# pc_healthypi_v1.net
KiCad netlist of a schematic drawn in EAGLE
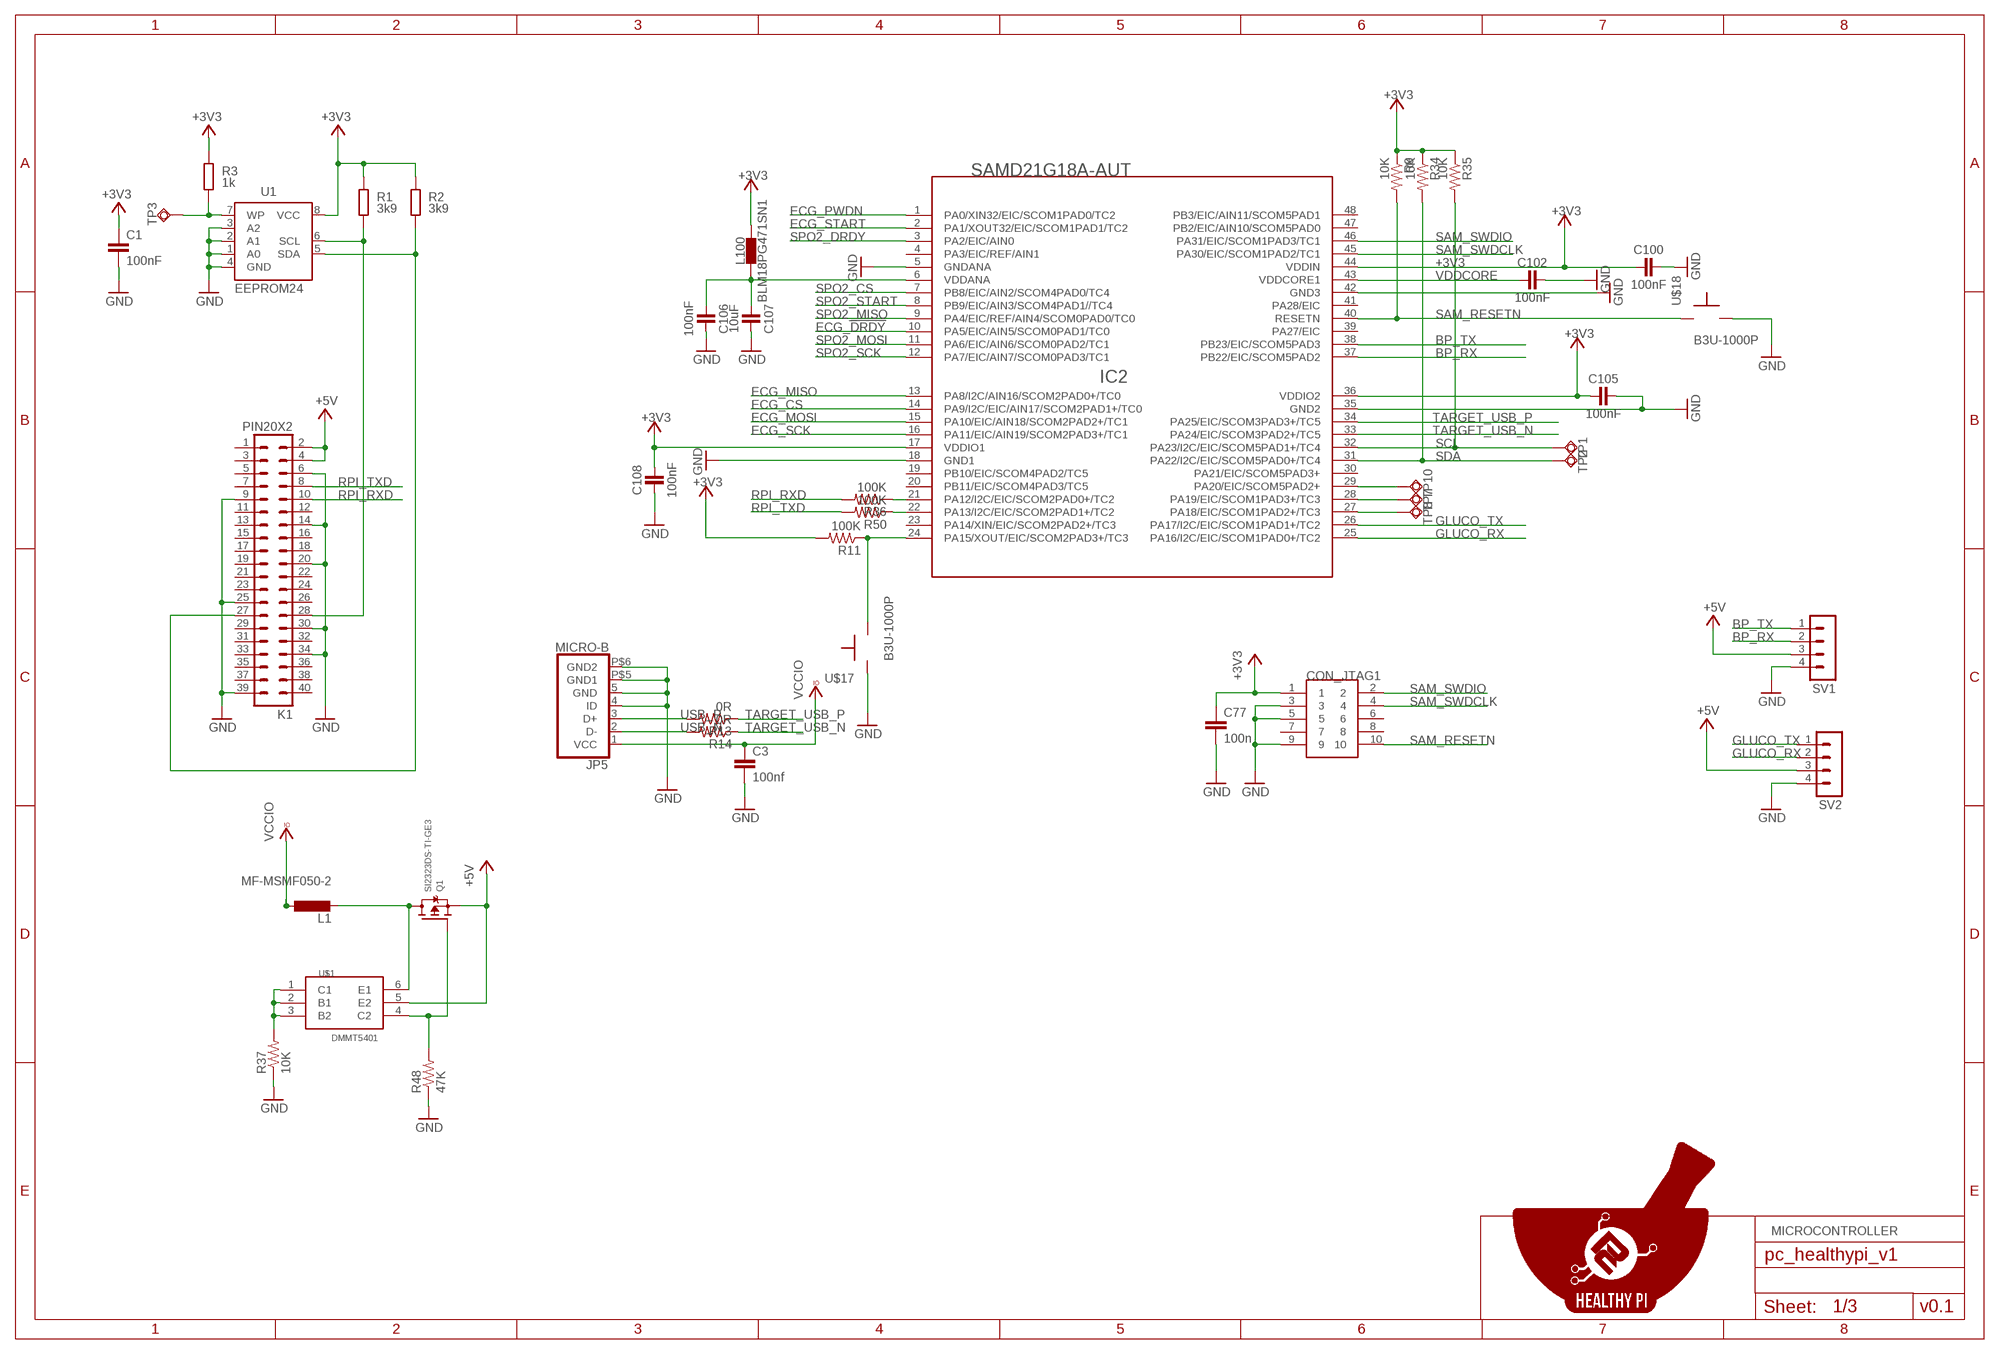
[diagram p0: schematic, sheet 1]
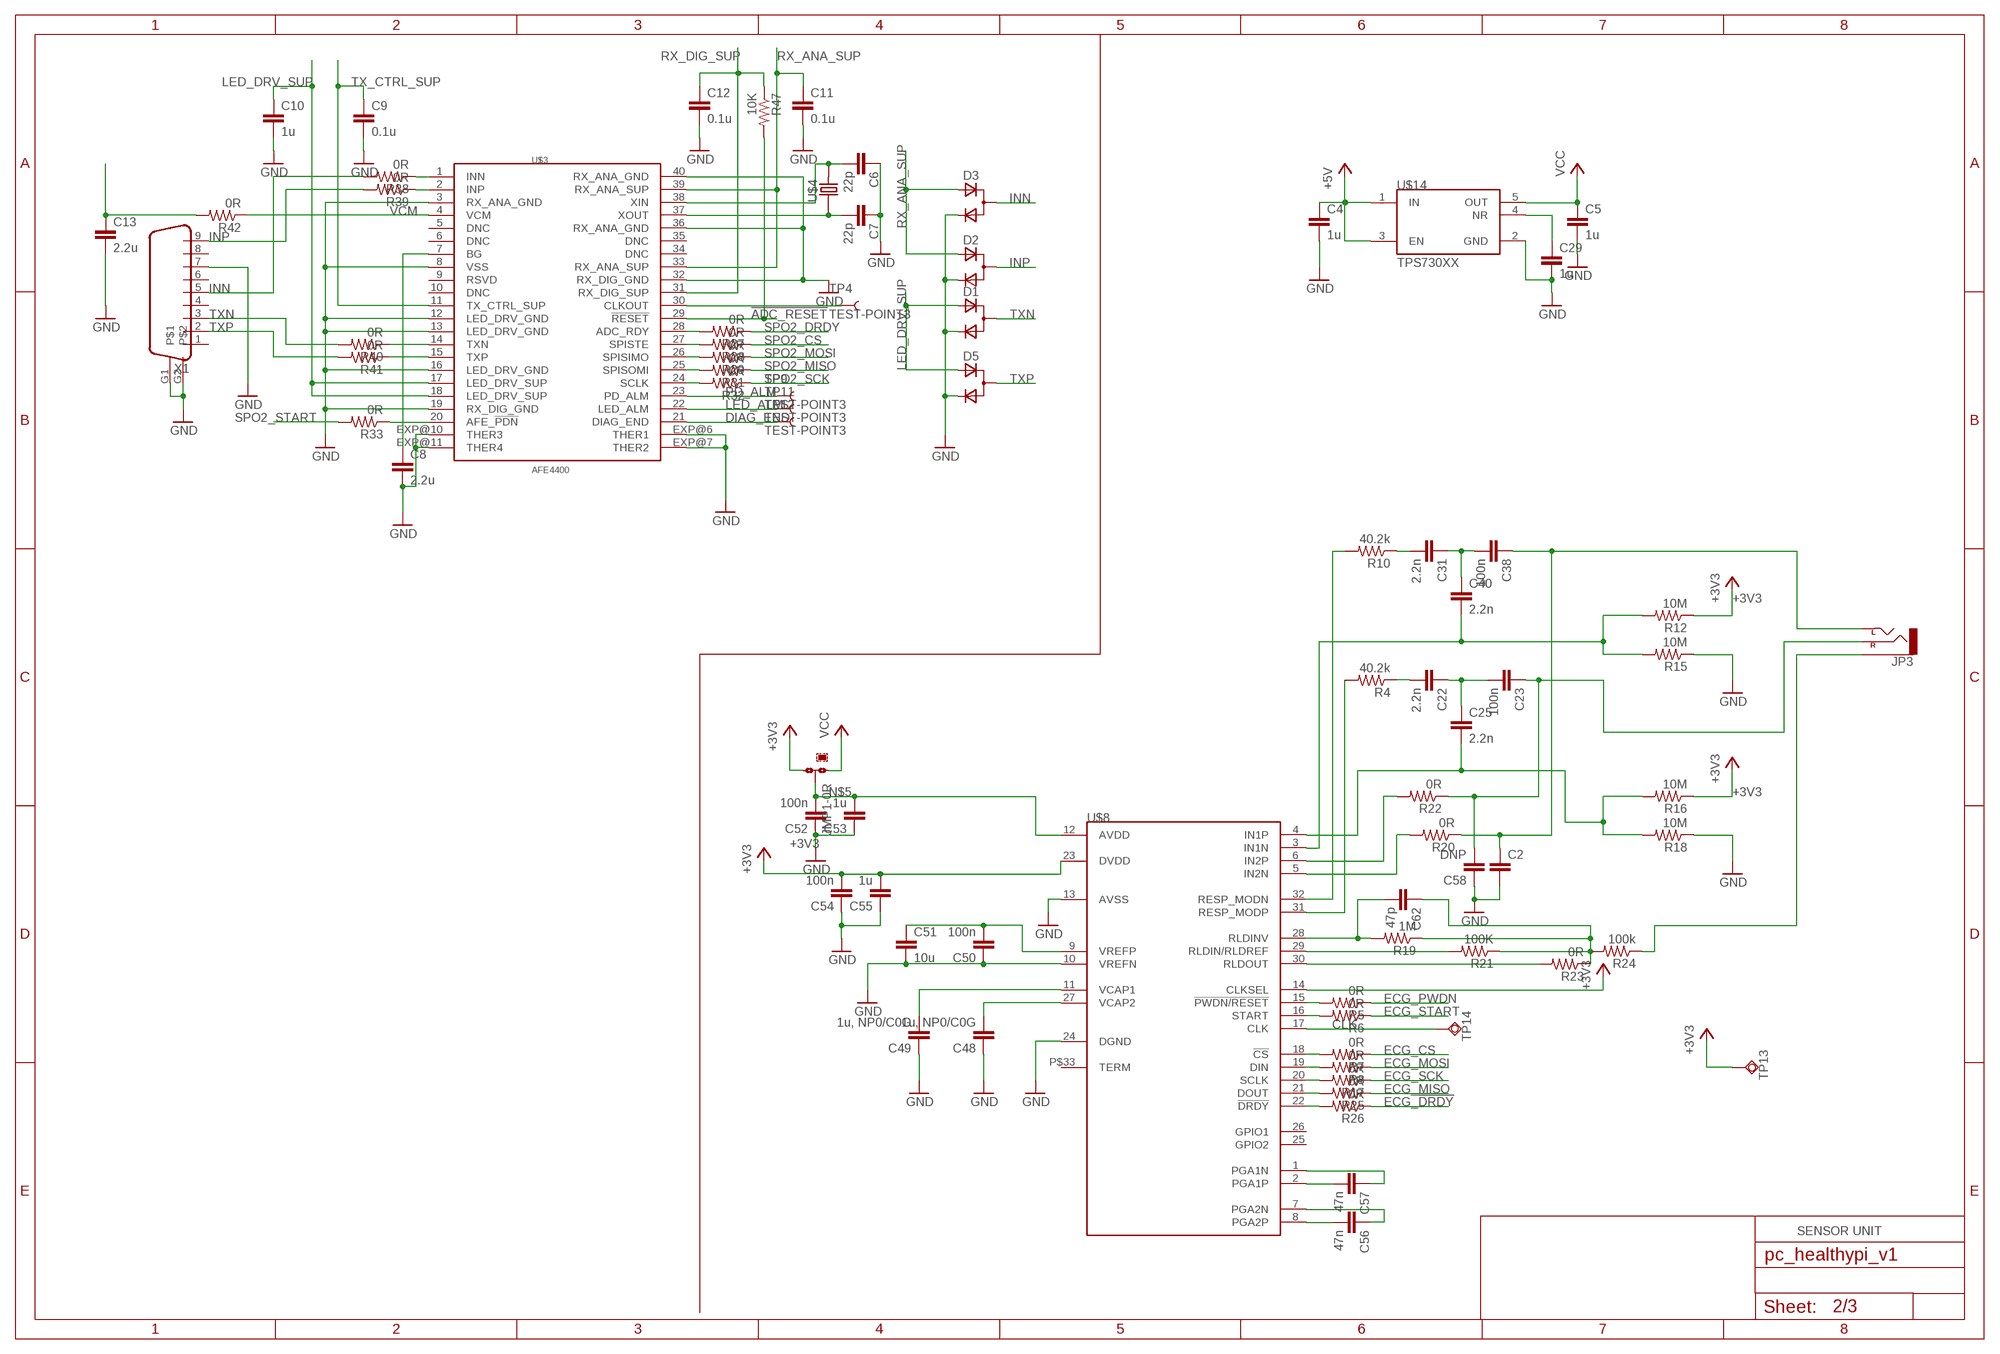
[diagram p1: schematic, sheet 2]
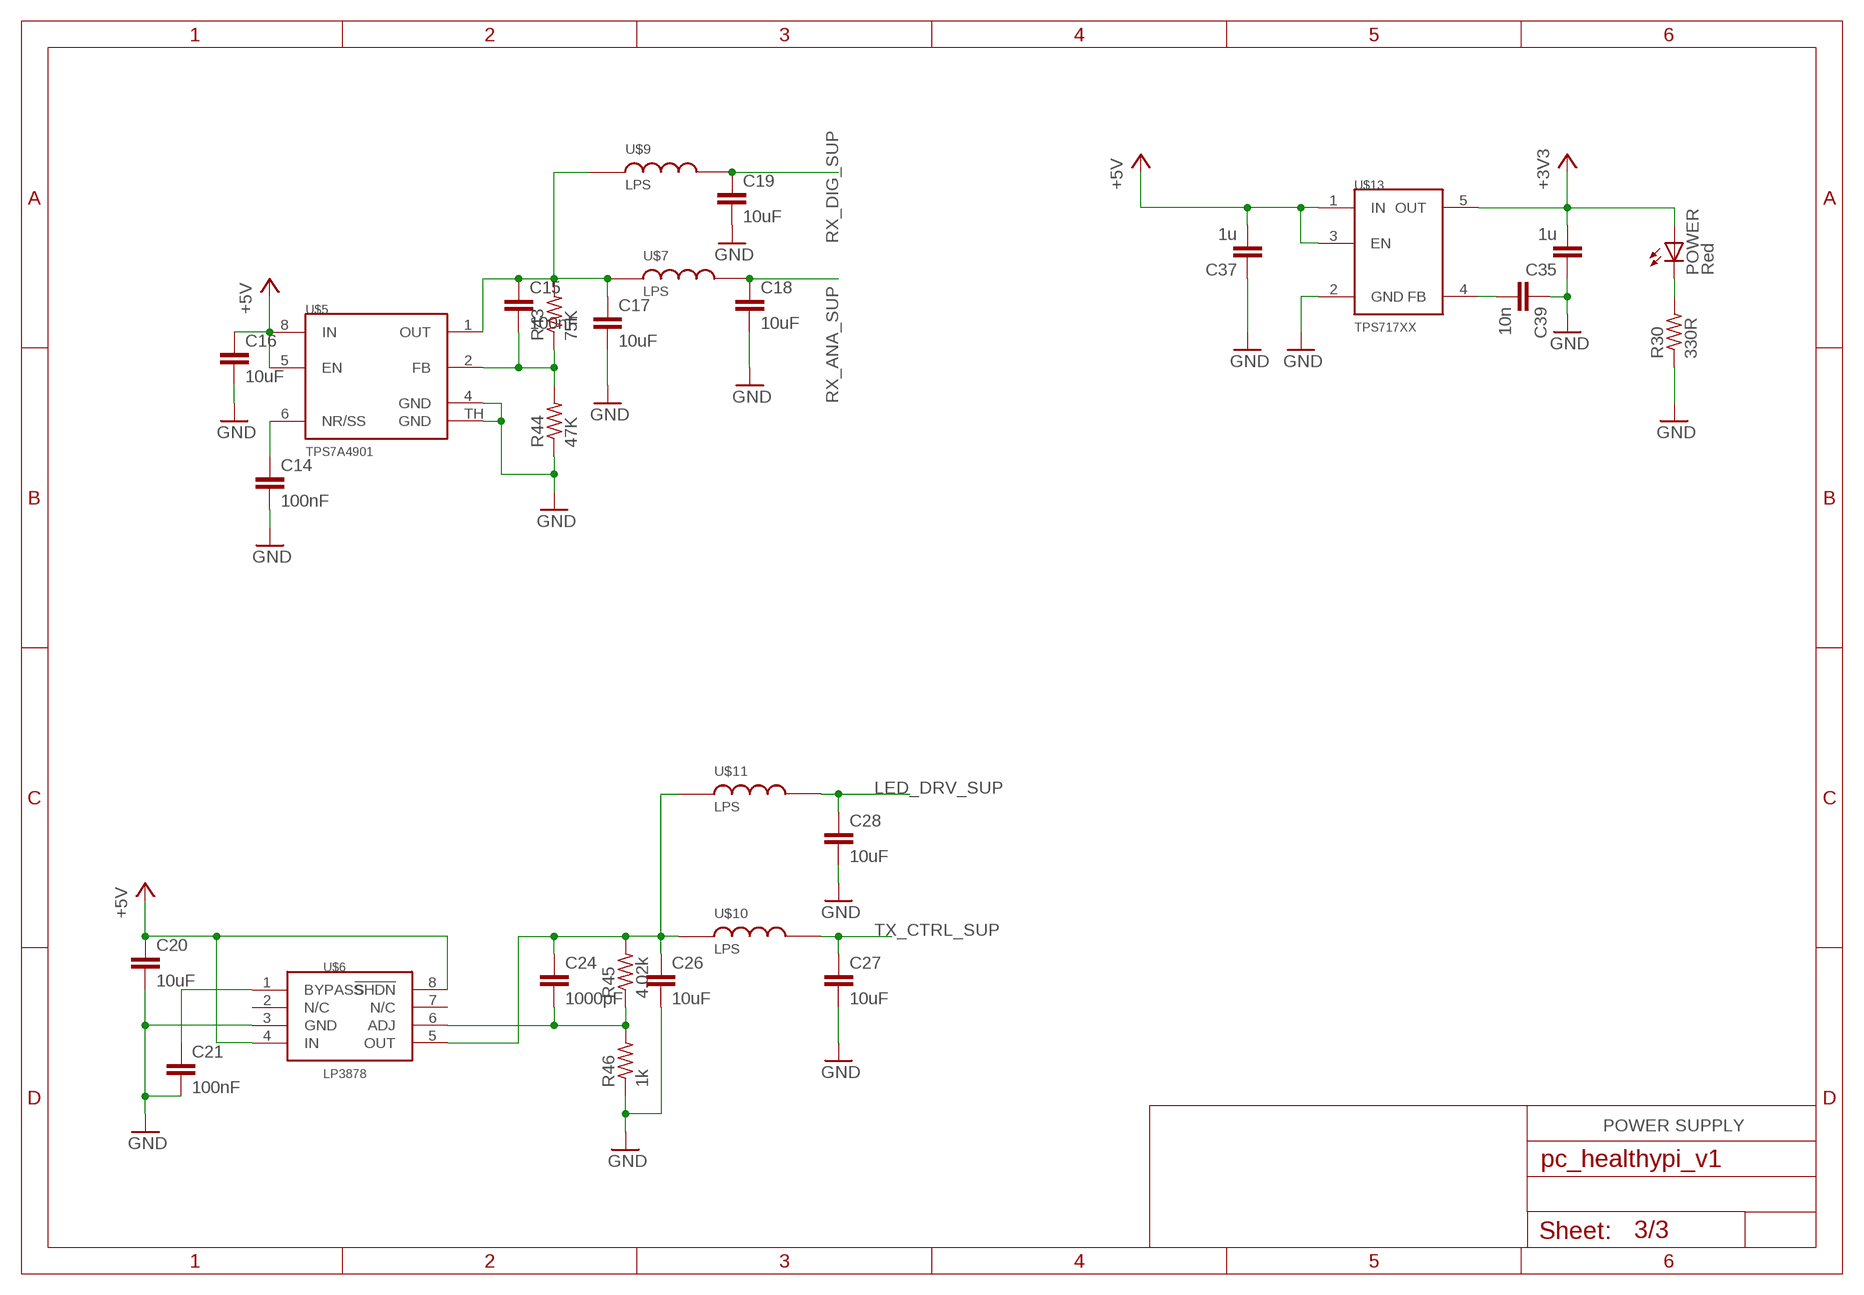
[diagram p2: schematic, sheet 3]

(export (version "E")
  (design (tool "Eeschema 10.0.6"))
  (components
    (comp (ref "C2")
      (value "C-EUC0402")
      (footprint "eagle-import:C0402")
      (libsource (lib "eagle-import") (part "C-EUC0402"))
    )
    (comp (ref "C4")
      (value "1u")
      (footprint "eagle-import:C0402")
      (libsource (lib "eagle-import") (part "C-EUC0402"))
    )
    (comp (ref "C5")
      (value "1u")
      (footprint "eagle-import:C0402")
      (libsource (lib "eagle-import") (part "C-EUC0402"))
    )
    (comp (ref "C6")
      (value "22p")
      (footprint "eagle-import:C0402")
      (libsource (lib "eagle-import") (part "C-EUC0402"))
    )
    (comp (ref "C7")
      (value "22p")
      (footprint "eagle-import:C0402")
      (libsource (lib "eagle-import") (part "C-EUC0402"))
    )
    (comp (ref "C8")
      (value "2.2u")
      (footprint "eagle-import:C0402")
      (libsource (lib "eagle-import") (part "C-EUC0402"))
    )
    (comp (ref "C9")
      (value "0.1u")
      (footprint "eagle-import:C0402")
      (libsource (lib "eagle-import") (part "C-EUC0402"))
    )
    (comp (ref "C10")
      (value "1u")
      (footprint "eagle-import:C0805")
      (libsource (lib "eagle-import") (part "C-EUC0805"))
    )
    (comp (ref "C11")
      (value "0.1u")
      (footprint "eagle-import:C0402")
      (libsource (lib "eagle-import") (part "C-EUC0402"))
    )
    (comp (ref "C12")
      (value "0.1u")
      (footprint "eagle-import:C0402")
      (libsource (lib "eagle-import") (part "C-EUC0402"))
    )
    (comp (ref "C13")
      (value "2.2u")
      (footprint "eagle-import:C0402")
      (libsource (lib "eagle-import") (part "C-EUC0402"))
    )
    (comp (ref "C22")
      (value "2.2n")
      (footprint "eagle-import:C0402")
      (libsource (lib "eagle-import") (part "C-EUC0402"))
    )
    (comp (ref "C23")
      (value "100n")
      (footprint "eagle-import:C0402")
      (libsource (lib "eagle-import") (part "C-EUC0402"))
    )
    (comp (ref "C25")
      (value "2.2n")
      (footprint "eagle-import:C0402")
      (libsource (lib "eagle-import") (part "C-EUC0402"))
    )
    (comp (ref "C29")
      (value "1u")
      (footprint "eagle-import:C0402")
      (libsource (lib "eagle-import") (part "C-EUC0402"))
    )
    (comp (ref "C31")
      (value "2.2n")
      (footprint "eagle-import:C0402")
      (libsource (lib "eagle-import") (part "C-EUC0402"))
    )
    (comp (ref "C38")
      (value "100n")
      (footprint "eagle-import:C0402")
      (libsource (lib "eagle-import") (part "C-EUC0402"))
    )
    (comp (ref "C40")
      (value "2.2n")
      (footprint "eagle-import:C0402")
      (libsource (lib "eagle-import") (part "C-EUC0402"))
    )
    (comp (ref "C48")
      (value "1u, NP0/C0G")
      (footprint "eagle-import:C0402")
      (libsource (lib "eagle-import") (part "C-EUC0402"))
    )
    (comp (ref "C49")
      (value "1u, NP0/C0G")
      (footprint "eagle-import:C0402")
      (libsource (lib "eagle-import") (part "C-EUC0402"))
    )
    (comp (ref "C50")
      (value "100n")
      (footprint "eagle-import:C0402")
      (libsource (lib "eagle-import") (part "C-EUC0402"))
    )
    (comp (ref "C51")
      (value "10u")
      (footprint "eagle-import:C0603")
      (libsource (lib "eagle-import") (part "resistor_C-EUC0603"))
    )
    (comp (ref "C52")
      (value "100n")
      (footprint "eagle-import:C0402")
      (libsource (lib "eagle-import") (part "C-EUC0402"))
    )
    (comp (ref "C53")
      (value "1u")
      (footprint "eagle-import:C0402")
      (libsource (lib "eagle-import") (part "C-EUC0402"))
    )
    (comp (ref "C54")
      (value "100n")
      (footprint "eagle-import:C0402")
      (libsource (lib "eagle-import") (part "C-EUC0402"))
    )
    (comp (ref "C55")
      (value "1u")
      (footprint "eagle-import:C0402")
      (libsource (lib "eagle-import") (part "C-EUC0402"))
    )
    (comp (ref "C56")
      (value "47n")
      (footprint "eagle-import:C0402")
      (libsource (lib "eagle-import") (part "C-EUC0402"))
    )
    (comp (ref "C57")
      (value "47n")
      (footprint "eagle-import:C0402")
      (libsource (lib "eagle-import") (part "C-EUC0402"))
    )
    (comp (ref "C58")
      (value "DNP")
      (footprint "eagle-import:C0402")
      (libsource (lib "eagle-import") (part "C-EUC0402"))
    )
    (comp (ref "C62")
      (value "47p")
      (footprint "eagle-import:C0402")
      (libsource (lib "eagle-import") (part "C-EUC0402"))
    )
    (comp (ref "D1")
      (value "D_ACACSOT323")
      (footprint "eagle-import:SOT323")
      (libsource (lib "eagle-import") (part "D_ACACSOT323"))
    )
    (comp (ref "D2")
      (value "D_ACACSOT323")
      (footprint "eagle-import:SOT323")
      (libsource (lib "eagle-import") (part "D_ACACSOT323"))
    )
    (comp (ref "D3")
      (value "D_ACACSOT323")
      (footprint "eagle-import:SOT323")
      (libsource (lib "eagle-import") (part "D_ACACSOT323"))
    )
    (comp (ref "D5")
      (value "D_ACACSOT323")
      (footprint "eagle-import:SOT323")
      (libsource (lib "eagle-import") (part "D_ACACSOT323"))
    )
    (comp (ref "JMP1")
      (value "0R-JUMPB")
      (footprint "eagle-import:B0R-JMP")
      (libsource (lib "eagle-import") (part "0R-JUMPB"))
    )
    (comp (ref "JP3")
      (value "AUDIO-JACKSMD2")
      (footprint "eagle-import:AUDIO-JACK-3.5MM-SMD")
      (libsource (lib "eagle-import") (part "AUDIO-JACKSMD2"))
    )
    (comp (ref "R4")
      (value "40.2k")
      (footprint "eagle-import:R0402")
      (libsource (lib "eagle-import") (part "R-US_R0402"))
    )
    (comp (ref "R5")
      (value "0R")
      (footprint "eagle-import:R0402")
      (libsource (lib "eagle-import") (part "R-US_R0402"))
    )
    (comp (ref "R6")
      (value "0R")
      (footprint "eagle-import:R0402")
      (libsource (lib "eagle-import") (part "R-US_R0402"))
    )
    (comp (ref "R7")
      (value "0R")
      (footprint "eagle-import:R0402")
      (libsource (lib "eagle-import") (part "R-US_R0402"))
    )
    (comp (ref "R8")
      (value "0R")
      (footprint "eagle-import:R0402")
      (libsource (lib "eagle-import") (part "R-US_R0402"))
    )
    (comp (ref "R10")
      (value "40.2k")
      (footprint "eagle-import:R0402")
      (libsource (lib "eagle-import") (part "R-US_R0402"))
    )
    (comp (ref "R12")
      (value "10M")
      (footprint "eagle-import:R0402")
      (libsource (lib "eagle-import") (part "R-US_R0402"))
    )
    (comp (ref "R15")
      (value "10M")
      (footprint "eagle-import:R0402")
      (libsource (lib "eagle-import") (part "R-US_R0402"))
    )
    (comp (ref "R16")
      (value "10M")
      (footprint "eagle-import:R0402")
      (libsource (lib "eagle-import") (part "R-US_R0402"))
    )
    (comp (ref "R17")
      (value "0R")
      (footprint "eagle-import:R0402")
      (libsource (lib "eagle-import") (part "R-US_R0402"))
    )
    (comp (ref "R18")
      (value "10M")
      (footprint "eagle-import:R0402")
      (libsource (lib "eagle-import") (part "R-US_R0402"))
    )
    (comp (ref "R19")
      (value "1M")
      (footprint "eagle-import:R0402")
      (libsource (lib "eagle-import") (part "R-US_R0402"))
    )
    (comp (ref "R20")
      (value "0R")
      (footprint "eagle-import:R0402")
      (libsource (lib "eagle-import") (part "R-US_R0402"))
    )
    (comp (ref "R21")
      (value "100K")
      (footprint "eagle-import:R0402")
      (libsource (lib "eagle-import") (part "R-US_R0402"))
    )
    (comp (ref "R22")
      (value "0R")
      (footprint "eagle-import:R0402")
      (libsource (lib "eagle-import") (part "R-US_R0402"))
    )
    (comp (ref "R23")
      (value "0R")
      (footprint "eagle-import:R0402")
      (libsource (lib "eagle-import") (part "R-US_R0402"))
    )
    (comp (ref "R24")
      (value "100k")
      (footprint "eagle-import:R0402")
      (libsource (lib "eagle-import") (part "R-US_R0402"))
    )
    (comp (ref "R25")
      (value "0R")
      (footprint "eagle-import:R0402")
      (libsource (lib "eagle-import") (part "R-US_R0402"))
    )
    (comp (ref "R26")
      (value "0R")
      (footprint "eagle-import:R0402")
      (libsource (lib "eagle-import") (part "R-US_R0402"))
    )
    (comp (ref "R27")
      (value "0R")
      (footprint "eagle-import:R0402")
      (libsource (lib "eagle-import") (part "R-US_R0402"))
    )
    (comp (ref "R28")
      (value "0R")
      (footprint "eagle-import:R0402")
      (libsource (lib "eagle-import") (part "R-US_R0402"))
    )
    (comp (ref "R29")
      (value "0R")
      (footprint "eagle-import:R0402")
      (libsource (lib "eagle-import") (part "R-US_R0402"))
    )
    (comp (ref "R31")
      (value "0R")
      (footprint "eagle-import:R0402")
      (libsource (lib "eagle-import") (part "R-US_R0402"))
    )
    (comp (ref "R32")
      (value "0R")
      (footprint "eagle-import:R0402")
      (libsource (lib "eagle-import") (part "R-US_R0402"))
    )
    (comp (ref "R33")
      (value "0R")
      (footprint "eagle-import:R0402")
      (libsource (lib "eagle-import") (part "R-US_R0402"))
    )
    (comp (ref "R38")
      (value "0R")
      (footprint "eagle-import:R0402")
      (libsource (lib "eagle-import") (part "R-US_R0402"))
    )
    (comp (ref "R39")
      (value "0R")
      (footprint "eagle-import:R0402")
      (libsource (lib "eagle-import") (part "R-US_R0402"))
    )
    (comp (ref "R40")
      (value "0R")
      (footprint "eagle-import:R0402")
      (libsource (lib "eagle-import") (part "R-US_R0402"))
    )
    (comp (ref "R41")
      (value "0R")
      (footprint "eagle-import:R0402")
      (libsource (lib "eagle-import") (part "R-US_R0402"))
    )
    (comp (ref "R42")
      (value "0R")
      (footprint "eagle-import:R0402")
      (libsource (lib "eagle-import") (part "R-US_R0402"))
    )
    (comp (ref "R47")
      (value "10K")
      (footprint "eagle-import:R0402")
      (libsource (lib "eagle-import") (part "R-US_R0402"))
    )
    (comp (ref "TP4")
      (value "TEST-POINT3")
      (footprint "eagle-import:PAD.03X.03")
      (libsource (lib "eagle-import") (part "TEST-POINT3"))
    )
    (comp (ref "TP9")
      (value "TEST-POINT3")
      (footprint "eagle-import:PAD.03X.03")
      (libsource (lib "eagle-import") (part "TEST-POINT3"))
    )
    (comp (ref "TP11")
      (value "TEST-POINT3")
      (footprint "eagle-import:PAD.03X.03")
      (libsource (lib "eagle-import") (part "TEST-POINT3"))
    )
    (comp (ref "TP12")
      (value "TEST-POINT3")
      (footprint "eagle-import:PAD.03X.03")
      (libsource (lib "eagle-import") (part "TEST-POINT3"))
    )
    (comp (ref "TP13")
      (value "TPSQB1,27")
      (footprint "eagle-import:B1,27")
      (libsource (lib "eagle-import") (part "TPSQB1,27"))
    )
    (comp (ref "TP14")
      (value "TPSQB1,27")
      (footprint "eagle-import:B1,27")
      (libsource (lib "eagle-import") (part "TPSQB1,27"))
    )
    (comp (ref "U$3")
      (value "AFE4400")
      (footprint "eagle-import:QFN-40")
      (libsource (lib "eagle-import") (part "AFE4400"))
    )
    (comp (ref "U$4")
      (value "ABM3")
      (footprint "eagle-import:ABM3")
      (libsource (lib "eagle-import") (part "ABM3"))
    )
    (comp (ref "U$8")
      (value "ADS1292RPVQFN32")
      (footprint "eagle-import:S-PVQFN-N32")
      (libsource (lib "eagle-import") (part "ADS1292RPVQFN32"))
    )
    (comp (ref "U$14")
      (value "TPS730XX")
      (footprint "eagle-import:SOT23-DBV")
      (libsource (lib "eagle-import") (part "TPS730XX"))
    )
    (comp (ref "X1")
      (value "DB9")
      (footprint "eagle-import:DB9")
      (libsource (lib "eagle-import") (part "DB9"))
    )
    (comp (ref "C1")
      (value "100nF")
      (footprint "eagle-import:C0805K")
      (libsource (lib "eagle-import") (part "resistor_C-EUC0805K"))
    )
    (comp (ref "C3")
      (value "100nf")
      (footprint "eagle-import:C0402")
      (libsource (lib "eagle-import") (part "C-EUC0402"))
    )
    (comp (ref "C77")
      (value "100n")
      (footprint "eagle-import:C0805")
      (libsource (lib "eagle-import") (part "C-EUC0805"))
    )
    (comp (ref "C100")
      (value "100nF")
      (footprint "eagle-import:C0805")
      (libsource (lib "eagle-import") (part "CAPACITORS-0805"))
    )
    (comp (ref "C102")
      (value "100nF")
      (footprint "eagle-import:C0805")
      (libsource (lib "eagle-import") (part "CAPACITORS-0805"))
    )
    (comp (ref "C105")
      (value "100nF")
      (footprint "eagle-import:C0805")
      (libsource (lib "eagle-import") (part "CAPACITORS-0805"))
    )
    (comp (ref "C106")
      (value "100nF")
      (footprint "eagle-import:C0805")
      (libsource (lib "eagle-import") (part "CAPACITORS-0805"))
    )
    (comp (ref "C107")
      (value "10uF")
      (footprint "eagle-import:C0805")
      (libsource (lib "eagle-import") (part "CAPACITORS-0805"))
    )
    (comp (ref "C108")
      (value "100nF")
      (footprint "eagle-import:C0805")
      (libsource (lib "eagle-import") (part "CAPACITORS-0805"))
    )
    (comp (ref "CON_JTAG1")
      (value "HDR-SMT-50MIL/5X2")
      (footprint "eagle-import:HDR-SMT-50MIL_5X2")
      (libsource (lib "eagle-import") (part "HDR-SMT-50MIL/5X2"))
    )
    (comp (ref "IC2")
      (value "SAMD21G18A-AUT")
      (footprint "eagle-import:TQFP48")
      (libsource (lib "eagle-import") (part "SAMD21G18A"))
    )
    (comp (ref "JP5")
      (value "MICRO-B")
      (footprint "eagle-import:MICRO-B")
      (libsource (lib "eagle-import") (part "MICRO-B"))
    )
    (comp (ref "K1")
      (value "PIN20X2")
      (footprint "eagle-import:PIN_20X2")
      (libsource (lib "eagle-import") (part "PIN20X2"))
    )
    (comp (ref "L1")
      (value "MF-MSMF050-2")
      (footprint "eagle-import:L1812")
      (libsource (lib "eagle-import") (part "L-EUL1812"))
    )
    (comp (ref "L100")
      (value "BLM18PG471SN1")
      (footprint "eagle-import:C0603")
      (libsource (lib "eagle-import") (part "INDUCTOR-0603"))
    )
    (comp (ref "Q1")
      (value "SI2323DS-TI-GE3")
      (footprint "eagle-import:SOT23-R")
      (libsource (lib "eagle-import") (part "MOSFET-P"))
    )
    (comp (ref "R1")
      (value "3k9")
      (footprint "eagle-import:M0805")
      (fields (field (name "TOLERANCE") "5%"))
      (libsource (lib "eagle-import") (part "R-EU_M0805"))
    )
    (comp (ref "R2")
      (value "3k9")
      (footprint "eagle-import:M0805")
      (fields (field (name "TOLERANCE") "5%"))
      (libsource (lib "eagle-import") (part "R-EU_M0805"))
    )
    (comp (ref "R3")
      (value "1k")
      (footprint "eagle-import:M0805")
      (fields (field (name "TOLERANCE") "5%"))
      (libsource (lib "eagle-import") (part "R-EU_M0805"))
    )
    (comp (ref "R9")
      (value "10K")
      (footprint "eagle-import:R0805")
      (libsource (lib "eagle-import") (part "R-US_R0805"))
    )
    (comp (ref "R11")
      (value "100K")
      (footprint "eagle-import:R0805")
      (libsource (lib "eagle-import") (part "R-US_R0805"))
    )
    (comp (ref "R13")
      (value "0R")
      (footprint "eagle-import:R0402")
      (libsource (lib "eagle-import") (part "R-US_R0402"))
    )
    (comp (ref "R14")
      (value "0R")
      (footprint "eagle-import:R0402")
      (libsource (lib "eagle-import") (part "R-US_R0402"))
    )
    (comp (ref "R34")
      (value "10K")
      (footprint "eagle-import:R0805")
      (libsource (lib "eagle-import") (part "R-US_R0805"))
    )
    (comp (ref "R35")
      (value "10K")
      (footprint "eagle-import:R0805")
      (libsource (lib "eagle-import") (part "R-US_R0805"))
    )
    (comp (ref "R36")
      (value "100K")
      (footprint "eagle-import:R0402")
      (libsource (lib "eagle-import") (part "R-US_R0402"))
    )
    (comp (ref "R37")
      (value "10K")
      (footprint "eagle-import:R0805")
      (libsource (lib "eagle-import") (part "R-US_R0805"))
    )
    (comp (ref "R48")
      (value "47K")
      (footprint "eagle-import:R0805")
      (libsource (lib "eagle-import") (part "R-US_R0805"))
    )
    (comp (ref "R50")
      (value "100K")
      (footprint "eagle-import:R0402")
      (libsource (lib "eagle-import") (part "R-US_R0402"))
    )
    (comp (ref "SV1")
      (value "MA04-1")
      (footprint "eagle-import:MA04-1")
      (libsource (lib "eagle-import") (part "MA04-1"))
    )
    (comp (ref "SV2")
      (value "MA04-1")
      (footprint "eagle-import:MA04-1")
      (libsource (lib "eagle-import") (part "MA04-1"))
    )
    (comp (ref "TP1")
      (value "TPSQB1,27")
      (footprint "eagle-import:B1,27")
      (libsource (lib "eagle-import") (part "TPSQB1,27"))
    )
    (comp (ref "TP2")
      (value "TPSQB1,27")
      (footprint "eagle-import:B1,27")
      (libsource (lib "eagle-import") (part "TPSQB1,27"))
    )
    (comp (ref "TP3")
      (value "TPSQB1,27")
      (footprint "eagle-import:B1,27")
      (libsource (lib "eagle-import") (part "TPSQB1,27"))
    )
    (comp (ref "TP7")
      (value "TPSQB1,27")
      (footprint "eagle-import:B1,27")
      (libsource (lib "eagle-import") (part "TPSQB1,27"))
    )
    (comp (ref "TP8")
      (value "TPSQB1,27")
      (footprint "eagle-import:B1,27")
      (libsource (lib "eagle-import") (part "TPSQB1,27"))
    )
    (comp (ref "TP10")
      (value "TPSQB1,27")
      (footprint "eagle-import:B1,27")
      (libsource (lib "eagle-import") (part "TPSQB1,27"))
    )
    (comp (ref "U$1")
      (value "DMMT5401")
      (footprint "eagle-import:SOT26")
      (libsource (lib "eagle-import") (part "DMMT5401"))
    )
    (comp (ref "U$15")
      (value "HEALTHYPI")
      (footprint "eagle-import:HEALTHYPI")
      (libsource (lib "eagle-import") (part "HEALTHYPI"))
    )
    (comp (ref "U$17")
      (value "B3U-1000P")
      (footprint "eagle-import:B3U-1000P")
      (libsource (lib "eagle-import") (part "B3U-1000P"))
    )
    (comp (ref "U$18")
      (value "B3U-1000P")
      (footprint "eagle-import:B3U-1000P")
      (libsource (lib "eagle-import") (part "B3U-1000P"))
    )
    (comp (ref "U1")
      (value "EEPROM24")
      (footprint "eagle-import:SOIC8")
      (libsource (lib "eagle-import") (part "EEPROM24"))
    )
    (comp (ref "C14")
      (value "100nF")
      (footprint "eagle-import:C0402")
      (libsource (lib "eagle-import") (part "C-EUC0402"))
    )
    (comp (ref "C15")
      (value "100nF")
      (footprint "eagle-import:C0402")
      (libsource (lib "eagle-import") (part "C-EUC0402"))
    )
    (comp (ref "C16")
      (value "10uF")
      (footprint "eagle-import:C0805")
      (libsource (lib "eagle-import") (part "C-EUC0805"))
    )
    (comp (ref "C17")
      (value "10uF")
      (footprint "eagle-import:C0805")
      (libsource (lib "eagle-import") (part "C-EUC0805"))
    )
    (comp (ref "C18")
      (value "10uF")
      (footprint "eagle-import:C0805")
      (libsource (lib "eagle-import") (part "C-EUC0805"))
    )
    (comp (ref "C19")
      (value "10uF")
      (footprint "eagle-import:C0805")
      (libsource (lib "eagle-import") (part "C-EUC0805"))
    )
    (comp (ref "C20")
      (value "10uF")
      (footprint "eagle-import:C0805")
      (libsource (lib "eagle-import") (part "C-EUC0805"))
    )
    (comp (ref "C21")
      (value "100nF")
      (footprint "eagle-import:C0402")
      (libsource (lib "eagle-import") (part "C-EUC0402"))
    )
    (comp (ref "C24")
      (value "1000pF")
      (footprint "eagle-import:C0402")
      (libsource (lib "eagle-import") (part "C-EUC0402"))
    )
    (comp (ref "C26")
      (value "10uF")
      (footprint "eagle-import:C0805")
      (libsource (lib "eagle-import") (part "C-EUC0805"))
    )
    (comp (ref "C27")
      (value "10uF")
      (footprint "eagle-import:C0805")
      (libsource (lib "eagle-import") (part "C-EUC0805"))
    )
    (comp (ref "C28")
      (value "10uF")
      (footprint "eagle-import:C0805")
      (libsource (lib "eagle-import") (part "C-EUC0805"))
    )
    (comp (ref "C35")
      (value "1u")
      (footprint "eagle-import:C0402")
      (libsource (lib "eagle-import") (part "C-EUC0402"))
    )
    (comp (ref "C37")
      (value "1u")
      (footprint "eagle-import:C0402")
      (libsource (lib "eagle-import") (part "C-EUC0402"))
    )
    (comp (ref "C39")
      (value "10n")
      (footprint "eagle-import:C0402")
      (libsource (lib "eagle-import") (part "C-EUC0402"))
    )
    (comp (ref "POWER")
      (value "Red")
      (footprint "eagle-import:CHIPLED_0603")
      (libsource (lib "eagle-import") (part "LEDCHIPLED_0603"))
    )
    (comp (ref "R30")
      (value "330R")
      (footprint "eagle-import:R0402")
      (libsource (lib "eagle-import") (part "R-US_R0402"))
    )
    (comp (ref "R43")
      (value "75K")
      (footprint "eagle-import:R0402")
      (libsource (lib "eagle-import") (part "R-US_R0402"))
    )
    (comp (ref "R44")
      (value "47K")
      (footprint "eagle-import:R0402")
      (libsource (lib "eagle-import") (part "R-US_R0402"))
    )
    (comp (ref "R45")
      (value "4.02k")
      (footprint "eagle-import:R0402")
      (libsource (lib "eagle-import") (part "R-US_R0402"))
    )
    (comp (ref "R46")
      (value "1k")
      (footprint "eagle-import:R0402")
      (libsource (lib "eagle-import") (part "R-US_R0402"))
    )
    (comp (ref "U$5")
      (value "TPS7A4901")
      (footprint "eagle-import:S-PDSO-G08")
      (libsource (lib "eagle-import") (part "TPS7A4901"))
    )
    (comp (ref "U$6")
      (value "LP3878")
      (footprint "eagle-import:DDA")
      (libsource (lib "eagle-import") (part "LP3878"))
    )
    (comp (ref "U$7")
      (value "LPS")
      (footprint "eagle-import:LPS")
      (libsource (lib "eagle-import") (part "LPS"))
    )
    (comp (ref "U$9")
      (value "LPS")
      (footprint "eagle-import:LPS")
      (libsource (lib "eagle-import") (part "LPS"))
    )
    (comp (ref "U$10")
      (value "LPS")
      (footprint "eagle-import:LPS")
      (libsource (lib "eagle-import") (part "LPS"))
    )
    (comp (ref "U$11")
      (value "LPS")
      (footprint "eagle-import:LPS")
      (libsource (lib "eagle-import") (part "LPS"))
    )
    (comp (ref "U$13")
      (value "TPS717XX")
      (footprint "eagle-import:SC70-5")
      (libsource (lib "eagle-import") (part "TPS717XX"))
    )
  )
  (nets
    (net (code "1") (name "+3V3") (class "Default")
      (node (ref "C1") (pin "1") (pinfunction "1_1") (pintype "passive"))
      (node (ref "C100") (pin "1") (pinfunction "1_1") (pintype "passive"))
      (node (ref "C105") (pin "1") (pinfunction "1_1") (pintype "passive"))
      (node (ref "C108") (pin "2") (pinfunction "2_2") (pintype "passive"))
      (node (ref "C35") (pin "2") (pinfunction "2_2") (pintype "passive"))
      (node (ref "C54") (pin "2") (pinfunction "2_2") (pintype "passive"))
      (node (ref "C55") (pin "2") (pinfunction "2_2") (pintype "passive"))
      (node (ref "C77") (pin "1") (pinfunction "1_1") (pintype "passive"))
      (node (ref "CON_JTAG1") (pin "1") (pinfunction "1_1") (pintype "bidirectional"))
      (node (ref "IC2") (pin "17") (pinfunction "VDDIO1_17") (pintype "power_in"))
      (node (ref "IC2") (pin "36") (pinfunction "VDDIO2_36") (pintype "power_in"))
      (node (ref "IC2") (pin "44") (pinfunction "VDDIN_44") (pintype "power_in"))
      (node (ref "JMP1") (pin "3") (pinfunction "3_3") (pintype "passive"))
      (node (ref "L100") (pin "2") (pinfunction "2_2") (pintype "passive"))
      (node (ref "POWER") (pin "A") (pinfunction "A_A") (pintype "passive"))
      (node (ref "R1") (pin "2") (pinfunction "2_2") (pintype "passive"))
      (node (ref "R11") (pin "2") (pinfunction "2_2") (pintype "passive"))
      (node (ref "R12") (pin "1") (pinfunction "1_1") (pintype "passive"))
      (node (ref "R16") (pin "1") (pinfunction "1_1") (pintype "passive"))
      (node (ref "R2") (pin "2") (pinfunction "2_2") (pintype "passive"))
      (node (ref "R3") (pin "2") (pinfunction "2_2") (pintype "passive"))
      (node (ref "R34") (pin "1") (pinfunction "1_1") (pintype "passive"))
      (node (ref "R35") (pin "1") (pinfunction "1_1") (pintype "passive"))
      (node (ref "R9") (pin "1") (pinfunction "1_1") (pintype "passive"))
      (node (ref "TP13") (pin "TP") (pinfunction "TP_TP") (pintype "input"))
      (node (ref "U$13") (pin "5") (pinfunction "OUT_5") (pintype "bidirectional"))
      (node (ref "U$8") (pin "14") (pinfunction "CLKSEL_14") (pintype "bidirectional"))
      (node (ref "U$8") (pin "23") (pinfunction "DVDD_23") (pintype "power_in"))
      (node (ref "U1") (pin "8") (pinfunction "VCC_8") (pintype "power_in"))
    )
    (net (code "2") (name "+5V") (class "Default")
      (node (ref "C16") (pin "1") (pinfunction "1_1") (pintype "passive"))
      (node (ref "C20") (pin "1") (pinfunction "1_1") (pintype "passive"))
      (node (ref "C37") (pin "2") (pinfunction "2_2") (pintype "passive"))
      (node (ref "C4") (pin "1") (pinfunction "1_1") (pintype "passive"))
      (node (ref "K1") (pin "2") (pinfunction "2_2") (pintype "passive"))
      (node (ref "K1") (pin "4") (pinfunction "4_4") (pintype "passive"))
      (node (ref "Q1") (pin "2") (pinfunction "S_2") (pintype "passive"))
      (node (ref "SV1") (pin "3") (pinfunction "3_3") (pintype "passive"))
      (node (ref "SV2") (pin "3") (pinfunction "3_3") (pintype "passive"))
      (node (ref "U$1") (pin "5") (pinfunction "E2_5") (pintype "bidirectional"))
      (node (ref "U$13") (pin "1") (pinfunction "IN_1") (pintype "bidirectional"))
      (node (ref "U$13") (pin "3") (pinfunction "EN_3") (pintype "bidirectional"))
      (node (ref "U$14") (pin "1") (pinfunction "IN_1") (pintype "bidirectional"))
      (node (ref "U$14") (pin "3") (pinfunction "EN_3") (pintype "bidirectional"))
      (node (ref "U$5") (pin "5") (pinfunction "EN_5") (pintype "bidirectional"))
      (node (ref "U$5") (pin "8") (pinfunction "IN_8") (pintype "bidirectional"))
      (node (ref "U$6") (pin "4") (pinfunction "IN_4") (pintype "bidirectional"))
      (node (ref "U$6") (pin "8") (pinfunction "~{SHDN}_8") (pintype "bidirectional"))
    )
    (net (code "3") (name "BP_RX") (class "Default")
      (node (ref "IC2") (pin "37") (pinfunction "PB22/EIC/SCOM5PAD2_37") (pintype "bidirectional"))
      (node (ref "SV1") (pin "2") (pinfunction "2_2") (pintype "passive"))
    )
    (net (code "4") (name "BP_TX") (class "Default")
      (node (ref "IC2") (pin "38") (pinfunction "PB23/EIC/SCOM5PAD3_38") (pintype "bidirectional"))
      (node (ref "SV1") (pin "1") (pinfunction "1_1") (pintype "passive"))
    )
    (net (code "5") (name "CLK") (class "Default")
      (node (ref "TP14") (pin "TP") (pinfunction "TP_TP") (pintype "input"))
      (node (ref "U$8") (pin "17") (pinfunction "CLK_17") (pintype "bidirectional"))
    )
    (net (code "6") (name "DIAG_END") (class "Default")
      (node (ref "TP12") (pin "P$1") (pinfunction "1_P$1") (pintype "bidirectional"))
      (node (ref "U$3") (pin "21") (pinfunction "DIAG_END_21") (pintype "bidirectional"))
    )
    (net (code "7") (name "ECG_CS") (class "Default")
      (node (ref "IC2") (pin "14") (pinfunction "PA9/I2C/EIC/AIN17/SCOM2PAD1+/TC0_14") (pintype "bidirectional"))
      (node (ref "R7") (pin "1") (pinfunction "1_1") (pintype "passive"))
    )
    (net (code "8") (name "ECG_MISO") (class "Default")
      (node (ref "IC2") (pin "13") (pinfunction "PA8/I2C/AIN16/SCOM2PAD0+/TC0_13") (pintype "bidirectional"))
      (node (ref "R25") (pin "1") (pinfunction "1_1") (pintype "passive"))
    )
    (net (code "9") (name "ECG_MOSI") (class "Default")
      (node (ref "IC2") (pin "15") (pinfunction "PA10/EIC/AIN18/SCOM2PAD2+/TC1_15") (pintype "bidirectional"))
      (node (ref "R8") (pin "1") (pinfunction "1_1") (pintype "passive"))
    )
    (net (code "10") (name "ECG_PWDN") (class "Default")
      (node (ref "IC2") (pin "1") (pinfunction "PA0/XIN32/EIC/SCOM1PAD0/TC2_1") (pintype "bidirectional"))
      (node (ref "R5") (pin "1") (pinfunction "1_1") (pintype "passive"))
    )
    (net (code "11") (name "ECG_SCK") (class "Default")
      (node (ref "IC2") (pin "16") (pinfunction "PA11/EIC/AIN19/SCOM2PAD3+/TC1_16") (pintype "bidirectional"))
      (node (ref "R17") (pin "1") (pinfunction "1_1") (pintype "passive"))
    )
    (net (code "12") (name "ECG_START") (class "Default")
      (node (ref "IC2") (pin "2") (pinfunction "PA1/XOUT32/EIC/SCOM1PAD1/TC2_2") (pintype "bidirectional"))
      (node (ref "R6") (pin "1") (pinfunction "1_1") (pintype "passive"))
    )
    (net (code "13") (name "ECG_~{DRDY}") (class "Default")
      (node (ref "IC2") (pin "10") (pinfunction "PA5/EIC/AIN5/SCOM0PAD1/TC0_10") (pintype "bidirectional"))
      (node (ref "R26") (pin "1") (pinfunction "1_1") (pintype "passive"))
    )
    (net (code "14") (name "GLUCO_RX") (class "Default")
      (node (ref "IC2") (pin "25") (pinfunction "PA16/I2C/EIC/SCOM1PAD0+/TC2_25") (pintype "bidirectional"))
      (node (ref "SV2") (pin "2") (pinfunction "2_2") (pintype "passive"))
    )
    (net (code "15") (name "GLUCO_TX") (class "Default")
      (node (ref "IC2") (pin "26") (pinfunction "PA17/I2C/EIC/SCOM1PAD1+/TC2_26") (pintype "bidirectional"))
      (node (ref "SV2") (pin "1") (pinfunction "1_1") (pintype "passive"))
    )
    (net (code "16") (name "GND") (class "Default")
      (node (ref "C1") (pin "2") (pinfunction "2_2") (pintype "passive"))
      (node (ref "C10") (pin "2") (pinfunction "2_2") (pintype "passive"))
      (node (ref "C100") (pin "2") (pinfunction "2_2") (pintype "passive"))
      (node (ref "C102") (pin "2") (pinfunction "2_2") (pintype "passive"))
      (node (ref "C105") (pin "2") (pinfunction "2_2") (pintype "passive"))
      (node (ref "C106") (pin "2") (pinfunction "2_2") (pintype "passive"))
      (node (ref "C107") (pin "2") (pinfunction "2_2") (pintype "passive"))
      (node (ref "C108") (pin "1") (pinfunction "1_1") (pintype "passive"))
      (node (ref "C11") (pin "2") (pinfunction "2_2") (pintype "passive"))
      (node (ref "C12") (pin "2") (pinfunction "2_2") (pintype "passive"))
      (node (ref "C13") (pin "2") (pinfunction "2_2") (pintype "passive"))
      (node (ref "C14") (pin "2") (pinfunction "2_2") (pintype "passive"))
      (node (ref "C16") (pin "2") (pinfunction "2_2") (pintype "passive"))
      (node (ref "C17") (pin "2") (pinfunction "2_2") (pintype "passive"))
      (node (ref "C18") (pin "2") (pinfunction "2_2") (pintype "passive"))
      (node (ref "C19") (pin "2") (pinfunction "2_2") (pintype "passive"))
      (node (ref "C2") (pin "2") (pinfunction "2_2") (pintype "passive"))
      (node (ref "C20") (pin "2") (pinfunction "2_2") (pintype "passive"))
      (node (ref "C21") (pin "2") (pinfunction "2_2") (pintype "passive"))
      (node (ref "C26") (pin "2") (pinfunction "2_2") (pintype "passive"))
      (node (ref "C27") (pin "2") (pinfunction "2_2") (pintype "passive"))
      (node (ref "C28") (pin "2") (pinfunction "2_2") (pintype "passive"))
      (node (ref "C29") (pin "2") (pinfunction "2_2") (pintype "passive"))
      (node (ref "C3") (pin "2") (pinfunction "2_2") (pintype "passive"))
      (node (ref "C35") (pin "1") (pinfunction "1_1") (pintype "passive"))
      (node (ref "C37") (pin "1") (pinfunction "1_1") (pintype "passive"))
      (node (ref "C39") (pin "1") (pinfunction "1_1") (pintype "passive"))
      (node (ref "C4") (pin "2") (pinfunction "2_2") (pintype "passive"))
      (node (ref "C48") (pin "1") (pinfunction "1_1") (pintype "passive"))
      (node (ref "C49") (pin "1") (pinfunction "1_1") (pintype "passive"))
      (node (ref "C5") (pin "2") (pinfunction "2_2") (pintype "passive"))
      (node (ref "C50") (pin "1") (pinfunction "1_1") (pintype "passive"))
      (node (ref "C51") (pin "2") (pinfunction "2_2") (pintype "passive"))
      (node (ref "C52") (pin "1") (pinfunction "1_1") (pintype "passive"))
      (node (ref "C53") (pin "1") (pinfunction "1_1") (pintype "passive"))
      (node (ref "C54") (pin "1") (pinfunction "1_1") (pintype "passive"))
      (node (ref "C55") (pin "1") (pinfunction "1_1") (pintype "passive"))
      (node (ref "C58") (pin "1") (pinfunction "1_1") (pintype "passive"))
      (node (ref "C6") (pin "1") (pinfunction "1_1") (pintype "passive"))
      (node (ref "C7") (pin "1") (pinfunction "1_1") (pintype "passive"))
      (node (ref "C77") (pin "2") (pinfunction "2_2") (pintype "passive"))
      (node (ref "C8") (pin "2") (pinfunction "2_2") (pintype "passive"))
      (node (ref "C9") (pin "2") (pinfunction "2_2") (pintype "passive"))
      (node (ref "CON_JTAG1") (pin "3") (pinfunction "3_3") (pintype "bidirectional"))
      (node (ref "CON_JTAG1") (pin "5") (pinfunction "5_5") (pintype "bidirectional"))
      (node (ref "CON_JTAG1") (pin "9") (pinfunction "9_9") (pintype "bidirectional"))
      (node (ref "D1") (pin "2") (pinfunction "C_2") (pintype "passive"))
      (node (ref "D2") (pin "2") (pinfunction "C_2") (pintype "passive"))
      (node (ref "D3") (pin "2") (pinfunction "C_2") (pintype "passive"))
      (node (ref "D5") (pin "2") (pinfunction "C_2") (pintype "passive"))
      (node (ref "IC2") (pin "18") (pinfunction "GND1_18") (pintype "power_in"))
      (node (ref "IC2") (pin "35") (pinfunction "GND2_35") (pintype "power_in"))
      (node (ref "IC2") (pin "42") (pinfunction "GND3_42") (pintype "power_in"))
      (node (ref "IC2") (pin "5") (pinfunction "GNDANA_5") (pintype "power_in"))
      (node (ref "JP5") (pin "4") (pinfunction "ID_4") (pintype "bidirectional"))
      (node (ref "JP5") (pin "5") (pinfunction "GND_5") (pintype "bidirectional"))
      (node (ref "JP5") (pin "P$5") (pinfunction "GND1_P$5") (pintype "bidirectional"))
      (node (ref "JP5") (pin "P$6") (pinfunction "GND2_P$6") (pintype "bidirectional"))
      (node (ref "K1") (pin "14") (pinfunction "14_14") (pintype "passive"))
      (node (ref "K1") (pin "20") (pinfunction "20_20") (pintype "passive"))
      (node (ref "K1") (pin "25") (pinfunction "25_25") (pintype "passive"))
      (node (ref "K1") (pin "30") (pinfunction "30_30") (pintype "passive"))
      (node (ref "K1") (pin "34") (pinfunction "34_34") (pintype "passive"))
      (node (ref "K1") (pin "39") (pinfunction "39_39") (pintype "passive"))
      (node (ref "K1") (pin "6") (pinfunction "6_6") (pintype "passive"))
      (node (ref "K1") (pin "9") (pinfunction "9_9") (pintype "passive"))
      (node (ref "R15") (pin "1") (pinfunction "1_1") (pintype "passive"))
      (node (ref "R18") (pin "1") (pinfunction "1_1") (pintype "passive"))
      (node (ref "R30") (pin "1") (pinfunction "1_1") (pintype "passive"))
      (node (ref "R37") (pin "1") (pinfunction "1_1") (pintype "passive"))
      (node (ref "R44") (pin "1") (pinfunction "1_1") (pintype "passive"))
      (node (ref "R46") (pin "1") (pinfunction "1_1") (pintype "passive"))
      (node (ref "R48") (pin "1") (pinfunction "1_1") (pintype "passive"))
      (node (ref "SV1") (pin "4") (pinfunction "4_4") (pintype "passive"))
      (node (ref "SV2") (pin "4") (pinfunction "4_4") (pintype "passive"))
      (node (ref "U$13") (pin "2") (pinfunction "GND_2") (pintype "bidirectional"))
      (node (ref "U$14") (pin "2") (pinfunction "GND_2") (pintype "bidirectional"))
      (node (ref "U$17") (pin "P$1") (pinfunction "P$1_P$1") (pintype "bidirectional"))
      (node (ref "U$18") (pin "P$2") (pinfunction "P$2_P$2") (pintype "bidirectional"))
      (node (ref "U$3") (pin "12") (pinfunction "LED_DRV_GND_12") (pintype "bidirectional"))
      (node (ref "U$3") (pin "13") (pinfunction "LED_DRV_GND_13") (pintype "bidirectional"))
      (node (ref "U$3") (pin "16") (pinfunction "LED_DRV_GND_16") (pintype "bidirectional"))
      (node (ref "U$3") (pin "19") (pinfunction "RX_DIG_GND_19") (pintype "bidirectional"))
      (node (ref "U$3") (pin "3") (pinfunction "RX_ANA_GND_3") (pintype "bidirectional"))
      (node (ref "U$3") (pin "32") (pinfunction "RX_DIG_GND_32") (pintype "bidirectional"))
      (node (ref "U$3") (pin "36") (pinfunction "RX_ANA_GND_36") (pintype "bidirectional"))
      (node (ref "U$3") (pin "40") (pinfunction "RX_ANA_GND_40") (pintype "bidirectional"))
      (node (ref "U$3") (pin "8") (pinfunction "VSS_8") (pintype "bidirectional"))
      (node (ref "U$3") (pin "EXP@10") (pinfunction "THER3_EXP@10") (pintype "bidirectional"))
      (node (ref "U$3") (pin "EXP@11") (pinfunction "THER4_EXP@11") (pintype "bidirectional"))
      (node (ref "U$3") (pin "EXP@6") (pinfunction "THER1_EXP@6") (pintype "bidirectional"))
      (node (ref "U$3") (pin "EXP@7") (pinfunction "THER2_EXP@7") (pintype "bidirectional"))
      (node (ref "U$5") (pin "4") (pinfunction "GND_4") (pintype "bidirectional"))
      (node (ref "U$5") (pin "TH") (pinfunction "GND_TH") (pintype "bidirectional"))
      (node (ref "U$6") (pin "3") (pinfunction "GND_3") (pintype "bidirectional"))
      (node (ref "U$8") (pin "10") (pinfunction "VREFN_10") (pintype "bidirectional"))
      (node (ref "U$8") (pin "13") (pinfunction "AVSS_13") (pintype "bidirectional"))
      (node (ref "U$8") (pin "24") (pinfunction "DGND_24") (pintype "bidirectional"))
      (node (ref "U1") (pin "1") (pinfunction "A0_1") (pintype "input"))
      (node (ref "U1") (pin "2") (pinfunction "A1_2") (pintype "input"))
      (node (ref "U1") (pin "3") (pinfunction "A2_3") (pintype "input"))
      (node (ref "U1") (pin "4") (pinfunction "GND_4") (pintype "power_in"))
      (node (ref "X1") (pin "7") (pinfunction "7_7") (pintype "passive"))
      (node (ref "X1") (pin "G1") (pinfunction "P$1_G1") (pintype "bidirectional"))
      (node (ref "X1") (pin "G2") (pinfunction "P$2_G2") (pintype "bidirectional"))
    )
    (net (code "17") (name "INN") (class "Default")
      (node (ref "D3") (pin "1") (pinfunction "CA_1") (pintype "passive"))
      (node (ref "R38") (pin "2") (pinfunction "2_2") (pintype "passive"))
      (node (ref "X1") (pin "5") (pinfunction "5_5") (pintype "passive"))
    )
    (net (code "18") (name "INP") (class "Default")
      (node (ref "D2") (pin "1") (pinfunction "CA_1") (pintype "passive"))
      (node (ref "R39") (pin "2") (pinfunction "2_2") (pintype "passive"))
      (node (ref "X1") (pin "9") (pinfunction "9_9") (pintype "passive"))
    )
    (net (code "19") (name "LED_ALM") (class "Default")
      (node (ref "TP11") (pin "P$1") (pinfunction "1_P$1") (pintype "bidirectional"))
      (node (ref "U$3") (pin "22") (pinfunction "LED_ALM_22") (pintype "bidirectional"))
    )
    (net (code "20") (name "LED_DRV_SUP") (class "Default")
      (node (ref "C10") (pin "1") (pinfunction "1_1") (pintype "passive"))
      (node (ref "C28") (pin "1") (pinfunction "1_1") (pintype "passive"))
      (node (ref "D1") (pin "3") (pinfunction "A_3") (pintype "passive"))
      (node (ref "D5") (pin "3") (pinfunction "A_3") (pintype "passive"))
      (node (ref "U$11") (pin "2") (pinfunction "P$2_2") (pintype "bidirectional"))
      (node (ref "U$3") (pin "17") (pinfunction "LED_DRV_SUP_17") (pintype "bidirectional"))
      (node (ref "U$3") (pin "18") (pinfunction "LED_DRV_SUP_18") (pintype "bidirectional"))
    )
    (net (code "21") (name "N$5") (class "Default")
      (node (ref "C52") (pin "2") (pinfunction "2_2") (pintype "passive"))
      (node (ref "C53") (pin "2") (pinfunction "2_2") (pintype "passive"))
      (node (ref "JMP1") (pin "2") (pinfunction "2_2") (pintype "passive"))
      (node (ref "U$8") (pin "12") (pinfunction "AVDD_12") (pintype "power_in"))
    )
    (net (code "22") (name "Net-(C13-Pad1)") (class "Default")
      (node (ref "C13") (pin "1") (pinfunction "1_1") (pintype "passive"))
      (node (ref "R42") (pin "2") (pinfunction "2_2") (pintype "passive"))
    )
    (net (code "23") (name "Net-(C22-Pad1)") (class "Default")
      (node (ref "C22") (pin "1") (pinfunction "1_1") (pintype "passive"))
      (node (ref "C23") (pin "2") (pinfunction "2_2") (pintype "passive"))
      (node (ref "C25") (pin "1") (pinfunction "1_1") (pintype "passive"))
    )
    (net (code "24") (name "Net-(C22-Pad2)") (class "Default")
      (node (ref "C22") (pin "2") (pinfunction "2_2") (pintype "passive"))
      (node (ref "R4") (pin "1") (pinfunction "1_1") (pintype "passive"))
    )
    (net (code "25") (name "Net-(C31-Pad1)") (class "Default")
      (node (ref "C31") (pin "1") (pinfunction "1_1") (pintype "passive"))
      (node (ref "C38") (pin "2") (pinfunction "2_2") (pintype "passive"))
      (node (ref "C40") (pin "1") (pinfunction "1_1") (pintype "passive"))
    )
    (net (code "26") (name "Net-(C31-Pad2)") (class "Default")
      (node (ref "C31") (pin "2") (pinfunction "2_2") (pintype "passive"))
      (node (ref "R10") (pin "1") (pinfunction "1_1") (pintype "passive"))
    )
    (net (code "27") (name "Net-(C62-Pad1)") (class "Default")
      (node (ref "C62") (pin "1") (pinfunction "1_1") (pintype "passive"))
      (node (ref "R19") (pin "1") (pinfunction "1_1") (pintype "passive"))
      (node (ref "R21") (pin "1") (pinfunction "1_1") (pintype "passive"))
      (node (ref "R23") (pin "1") (pinfunction "1_1") (pintype "passive"))
      (node (ref "R24") (pin "2") (pinfunction "2_2") (pintype "passive"))
    )
    (net (code "28") (name "Net-(IC2-PA12{slash}I2C{slash}EIC{slash}SCOM2PAD0+{slash}TC2)") (class "Default")
      (node (ref "IC2") (pin "21") (pinfunction "PA12/I2C/EIC/SCOM2PAD0+/TC2_21") (pintype "bidirectional"))
      (node (ref "R36") (pin "1") (pinfunction "1_1") (pintype "passive"))
    )
    (net (code "29") (name "Net-(IC2-PA13{slash}I2C{slash}EIC{slash}SCOM2PAD1+{slash}TC2)") (class "Default")
      (node (ref "IC2") (pin "22") (pinfunction "PA13/I2C/EIC/SCOM2PAD1+/TC2_22") (pintype "bidirectional"))
      (node (ref "R50") (pin "1") (pinfunction "1_1") (pintype "passive"))
    )
    (net (code "30") (name "Net-(IC2-PA15{slash}XOUT{slash}EIC{slash}SCOM2PAD3+{slash}TC3)") (class "Default")
      (node (ref "IC2") (pin "24") (pinfunction "PA15/XOUT/EIC/SCOM2PAD3+/TC3_24") (pintype "bidirectional"))
      (node (ref "R11") (pin "1") (pinfunction "1_1") (pintype "passive"))
      (node (ref "U$17") (pin "P$2") (pinfunction "P$2_P$2") (pintype "bidirectional"))
    )
    (net (code "31") (name "Net-(IC2-PA18{slash}EIC{slash}SCOM1PAD2+{slash}TC3)") (class "Default")
      (node (ref "IC2") (pin "27") (pinfunction "PA18/EIC/SCOM1PAD2+/TC3_27") (pintype "bidirectional"))
      (node (ref "TP8") (pin "TP") (pinfunction "TP_TP") (pintype "input"))
    )
    (net (code "32") (name "Net-(IC2-PA19{slash}EIC{slash}SCOM1PAD3+{slash}TC3)") (class "Default")
      (node (ref "IC2") (pin "28") (pinfunction "PA19/EIC/SCOM1PAD3+/TC3_28") (pintype "bidirectional"))
      (node (ref "TP7") (pin "TP") (pinfunction "TP_TP") (pintype "input"))
    )
    (net (code "33") (name "Net-(IC2-PA20{slash}EIC{slash}SCOM5PAD2+)") (class "Default")
      (node (ref "IC2") (pin "29") (pinfunction "PA20/EIC/SCOM5PAD2+_29") (pintype "bidirectional"))
      (node (ref "TP10") (pin "TP") (pinfunction "TP_TP") (pintype "input"))
    )
    (net (code "34") (name "Net-(IC2-VDDANA)") (class "Default")
      (node (ref "C106") (pin "1") (pinfunction "1_1") (pintype "passive"))
      (node (ref "C107") (pin "1") (pinfunction "1_1") (pintype "passive"))
      (node (ref "IC2") (pin "6") (pinfunction "VDDANA_6") (pintype "power_in"))
      (node (ref "L100") (pin "1") (pinfunction "1_1") (pintype "passive"))
    )
    (net (code "35") (name "Net-(JP3-LEFT)") (class "Default")
      (node (ref "C2") (pin "1") (pinfunction "1_1") (pintype "passive"))
      (node (ref "C38") (pin "1") (pinfunction "1_1") (pintype "passive"))
      (node (ref "JP3") (pin "TIP") (pinfunction "LEFT_TIP") (pintype "bidirectional"))
      (node (ref "R20") (pin "1") (pinfunction "1_1") (pintype "passive"))
    )
    (net (code "36") (name "Net-(JP3-PadSLEEVE)") (class "Default")
      (node (ref "JP3") (pin "SLEEVE") (pinfunction "SLEEVE_SLEEVE") (pintype "bidirectional"))
      (node (ref "R24") (pin "1") (pinfunction "1_1") (pintype "passive"))
    )
    (net (code "37") (name "Net-(JP3-RIGHT)") (class "Default")
      (node (ref "C23") (pin "1") (pinfunction "1_1") (pintype "passive"))
      (node (ref "C58") (pin "2") (pinfunction "2_2") (pintype "passive"))
      (node (ref "JP3") (pin "RING") (pinfunction "RIGHT_RING") (pintype "bidirectional"))
      (node (ref "R22") (pin "1") (pinfunction "1_1") (pintype "passive"))
    )
    (net (code "38") (name "Net-(POWER-PadC)") (class "Default")
      (node (ref "POWER") (pin "C") (pinfunction "C_C") (pintype "passive"))
      (node (ref "R30") (pin "2") (pinfunction "2_2") (pintype "passive"))
    )
    (net (code "39") (name "Net-(Q1-D)") (class "Default")
      (node (ref "L1") (pin "2") (pinfunction "2_2") (pintype "passive"))
      (node (ref "Q1") (pin "3") (pinfunction "D_3") (pintype "passive"))
      (node (ref "U$1") (pin "6") (pinfunction "E1_6") (pintype "bidirectional"))
    )
    (net (code "40") (name "Net-(Q1-G)") (class "Default")
      (node (ref "Q1") (pin "1") (pinfunction "G_1") (pintype "passive"))
      (node (ref "R48") (pin "2") (pinfunction "2_2") (pintype "passive"))
      (node (ref "U$1") (pin "4") (pinfunction "C2_4") (pintype "bidirectional"))
    )
    (net (code "41") (name "Net-(TP4-1)") (class "Default")
      (node (ref "TP4") (pin "P$1") (pinfunction "1_P$1") (pintype "bidirectional"))
      (node (ref "U$3") (pin "30") (pinfunction "CLKOUT_30") (pintype "bidirectional"))
    )
    (net (code "42") (name "Net-(U$1-B1)") (class "Default")
      (node (ref "R37") (pin "2") (pinfunction "2_2") (pintype "passive"))
      (node (ref "U$1") (pin "1") (pinfunction "C1_1") (pintype "bidirectional"))
      (node (ref "U$1") (pin "2") (pinfunction "B1_2") (pintype "bidirectional"))
      (node (ref "U$1") (pin "3") (pinfunction "B2_3") (pintype "bidirectional"))
    )
    (net (code "43") (name "Net-(U$3-ADC_RDY)") (class "Default")
      (node (ref "R27") (pin "2") (pinfunction "2_2") (pintype "passive"))
      (node (ref "U$3") (pin "28") (pinfunction "ADC_RDY_28") (pintype "bidirectional"))
    )
    (net (code "44") (name "Net-(U$3-AFE_~{PDN})") (class "Default")
      (node (ref "R33") (pin "1") (pinfunction "1_1") (pintype "passive"))
      (node (ref "U$3") (pin "20") (pinfunction "AFE_~{PDN}_20") (pintype "bidirectional"))
    )
    (net (code "45") (name "Net-(U$3-BG)") (class "Default")
      (node (ref "C8") (pin "1") (pinfunction "1_1") (pintype "passive"))
      (node (ref "U$3") (pin "7") (pinfunction "BG_7") (pintype "bidirectional"))
    )
    (net (code "46") (name "Net-(U$3-INN)") (class "Default")
      (node (ref "R38") (pin "1") (pinfunction "1_1") (pintype "passive"))
      (node (ref "U$3") (pin "1") (pinfunction "INN_1") (pintype "bidirectional"))
    )
    (net (code "47") (name "Net-(U$3-INP)") (class "Default")
      (node (ref "R39") (pin "1") (pinfunction "1_1") (pintype "passive"))
      (node (ref "U$3") (pin "2") (pinfunction "INP_2") (pintype "bidirectional"))
    )
    (net (code "48") (name "Net-(U$3-SCLK)") (class "Default")
      (node (ref "R32") (pin "2") (pinfunction "2_2") (pintype "passive"))
      (node (ref "U$3") (pin "24") (pinfunction "SCLK_24") (pintype "bidirectional"))
    )
    (net (code "49") (name "Net-(U$3-SPISIMO)") (class "Default")
      (node (ref "R29") (pin "2") (pinfunction "2_2") (pintype "passive"))
      (node (ref "U$3") (pin "26") (pinfunction "SPISIMO_26") (pintype "bidirectional"))
    )
    (net (code "50") (name "Net-(U$3-SPISOMI)") (class "Default")
      (node (ref "R31") (pin "2") (pinfunction "2_2") (pintype "passive"))
      (node (ref "U$3") (pin "25") (pinfunction "SPISOMI_25") (pintype "bidirectional"))
    )
    (net (code "51") (name "Net-(U$3-SPISTE)") (class "Default")
      (node (ref "R28") (pin "2") (pinfunction "2_2") (pintype "passive"))
      (node (ref "U$3") (pin "27") (pinfunction "SPISTE_27") (pintype "bidirectional"))
    )
    (net (code "52") (name "Net-(U$3-TXN)") (class "Default")
      (node (ref "R40") (pin "1") (pinfunction "1_1") (pintype "passive"))
      (node (ref "U$3") (pin "14") (pinfunction "TXN_14") (pintype "bidirectional"))
    )
    (net (code "53") (name "Net-(U$3-TXP)") (class "Default")
      (node (ref "R41") (pin "1") (pinfunction "1_1") (pintype "passive"))
      (node (ref "U$3") (pin "15") (pinfunction "TXP_15") (pintype "bidirectional"))
    )
    (net (code "54") (name "Net-(U$3-XIN)") (class "Default")
      (node (ref "C6") (pin "2") (pinfunction "2_2") (pintype "passive"))
      (node (ref "U$3") (pin "38") (pinfunction "XIN_38") (pintype "bidirectional"))
      (node (ref "U$4") (pin "2") (pinfunction "2_2") (pintype "passive"))
    )
    (net (code "55") (name "Net-(U$3-XOUT)") (class "Default")
      (node (ref "C7") (pin "2") (pinfunction "2_2") (pintype "passive"))
      (node (ref "U$3") (pin "37") (pinfunction "XOUT_37") (pintype "bidirectional"))
      (node (ref "U$4") (pin "1") (pinfunction "1_1") (pintype "passive"))
    )
    (net (code "56") (name "Net-(U$5-FB)") (class "Default")
      (node (ref "C15") (pin "2") (pinfunction "2_2") (pintype "passive"))
      (node (ref "R43") (pin "1") (pinfunction "1_1") (pintype "passive"))
      (node (ref "R44") (pin "2") (pinfunction "2_2") (pintype "passive"))
      (node (ref "U$5") (pin "2") (pinfunction "FB_2") (pintype "bidirectional"))
    )
    (net (code "57") (name "Net-(U$5-NR{slash}SS)") (class "Default")
      (node (ref "C14") (pin "1") (pinfunction "1_1") (pintype "passive"))
      (node (ref "U$5") (pin "6") (pinfunction "NR/SS_6") (pintype "bidirectional"))
    )
    (net (code "58") (name "Net-(U$5-OUT)") (class "Default")
      (node (ref "C15") (pin "1") (pinfunction "1_1") (pintype "passive"))
      (node (ref "C17") (pin "1") (pinfunction "1_1") (pintype "passive"))
      (node (ref "R43") (pin "2") (pinfunction "2_2") (pintype "passive"))
      (node (ref "U$5") (pin "1") (pinfunction "OUT_1") (pintype "bidirectional"))
      (node (ref "U$7") (pin "1") (pinfunction "P$1_1") (pintype "bidirectional"))
      (node (ref "U$9") (pin "1") (pinfunction "P$1_1") (pintype "bidirectional"))
    )
    (net (code "59") (name "Net-(U$6-ADJ)") (class "Default")
      (node (ref "C24") (pin "2") (pinfunction "2_2") (pintype "passive"))
      (node (ref "R45") (pin "1") (pinfunction "1_1") (pintype "passive"))
      (node (ref "R46") (pin "2") (pinfunction "2_2") (pintype "passive"))
      (node (ref "U$6") (pin "6") (pinfunction "ADJ_6") (pintype "bidirectional"))
    )
    (net (code "60") (name "Net-(U$6-BYPASS)") (class "Default")
      (node (ref "C21") (pin "1") (pinfunction "1_1") (pintype "passive"))
      (node (ref "U$6") (pin "1") (pinfunction "BYPASS_1") (pintype "bidirectional"))
    )
    (net (code "61") (name "Net-(U$8-DIN)") (class "Default")
      (node (ref "R8") (pin "2") (pinfunction "2_2") (pintype "passive"))
      (node (ref "U$8") (pin "19") (pinfunction "DIN_19") (pintype "bidirectional"))
    )
    (net (code "62") (name "Net-(U$8-DOUT)") (class "Default")
      (node (ref "R25") (pin "2") (pinfunction "2_2") (pintype "passive"))
      (node (ref "U$8") (pin "21") (pinfunction "DOUT_21") (pintype "bidirectional"))
    )
    (net (code "63") (name "Net-(U$8-IN1N)") (class "Default")
      (node (ref "C40") (pin "2") (pinfunction "2_2") (pintype "passive"))
      (node (ref "R12") (pin "2") (pinfunction "2_2") (pintype "passive"))
      (node (ref "R15") (pin "2") (pinfunction "2_2") (pintype "passive"))
      (node (ref "U$8") (pin "3") (pinfunction "IN1N_3") (pintype "input"))
    )
    (net (code "64") (name "Net-(U$8-IN1P)") (class "Default")
      (node (ref "C25") (pin "2") (pinfunction "2_2") (pintype "passive"))
      (node (ref "R16") (pin "2") (pinfunction "2_2") (pintype "passive"))
      (node (ref "R18") (pin "2") (pinfunction "2_2") (pintype "passive"))
      (node (ref "U$8") (pin "4") (pinfunction "IN1P_4") (pintype "input"))
    )
    (net (code "65") (name "Net-(U$8-IN2N)") (class "Default")
      (node (ref "R20") (pin "2") (pinfunction "2_2") (pintype "passive"))
      (node (ref "U$8") (pin "5") (pinfunction "IN2N_5") (pintype "input"))
    )
    (net (code "66") (name "Net-(U$8-IN2P)") (class "Default")
      (node (ref "R22") (pin "2") (pinfunction "2_2") (pintype "passive"))
      (node (ref "U$8") (pin "6") (pinfunction "IN2P_6") (pintype "input"))
    )
    (net (code "67") (name "Net-(U$8-PGA1N)") (class "Default")
      (node (ref "C57") (pin "1") (pinfunction "1_1") (pintype "passive"))
      (node (ref "U$8") (pin "1") (pinfunction "PGA1N_1") (pintype "bidirectional"))
    )
    (net (code "68") (name "Net-(U$8-PGA1P)") (class "Default")
      (node (ref "C57") (pin "2") (pinfunction "2_2") (pintype "passive"))
      (node (ref "U$8") (pin "2") (pinfunction "PGA1P_2") (pintype "bidirectional"))
    )
    (net (code "69") (name "Net-(U$8-PGA2N)") (class "Default")
      (node (ref "C56") (pin "1") (pinfunction "1_1") (pintype "passive"))
      (node (ref "U$8") (pin "7") (pinfunction "PGA2N_7") (pintype "bidirectional"))
    )
    (net (code "70") (name "Net-(U$8-PGA2P)") (class "Default")
      (node (ref "C56") (pin "2") (pinfunction "2_2") (pintype "passive"))
      (node (ref "U$8") (pin "8") (pinfunction "PGA2P_8") (pintype "bidirectional"))
    )
    (net (code "71") (name "Net-(U$8-RESP_MODN)") (class "Default")
      (node (ref "R10") (pin "2") (pinfunction "2_2") (pintype "passive"))
      (node (ref "U$8") (pin "32") (pinfunction "RESP_MODN_32") (pintype "bidirectional"))
    )
    (net (code "72") (name "Net-(U$8-RESP_MODP)") (class "Default")
      (node (ref "R4") (pin "2") (pinfunction "2_2") (pintype "passive"))
      (node (ref "U$8") (pin "31") (pinfunction "RESP_MODP_31") (pintype "bidirectional"))
    )
    (net (code "73") (name "Net-(U$8-RLDINV)") (class "Default")
      (node (ref "C62") (pin "2") (pinfunction "2_2") (pintype "passive"))
      (node (ref "R19") (pin "2") (pinfunction "2_2") (pintype "passive"))
      (node (ref "U$8") (pin "28") (pinfunction "RLDINV_28") (pintype "bidirectional"))
    )
    (net (code "74") (name "Net-(U$8-RLDIN{slash}RLDREF)") (class "Default")
      (node (ref "R21") (pin "2") (pinfunction "2_2") (pintype "passive"))
      (node (ref "U$8") (pin "29") (pinfunction "RLDIN/RLDREF_29") (pintype "bidirectional"))
    )
    (net (code "75") (name "Net-(U$8-RLDOUT)") (class "Default")
      (node (ref "R23") (pin "2") (pinfunction "2_2") (pintype "passive"))
      (node (ref "U$8") (pin "30") (pinfunction "RLDOUT_30") (pintype "bidirectional"))
    )
    (net (code "76") (name "Net-(U$8-SCLK)") (class "Default")
      (node (ref "R17") (pin "2") (pinfunction "2_2") (pintype "passive"))
      (node (ref "U$8") (pin "20") (pinfunction "SCLK_20") (pintype "bidirectional"))
    )
    (net (code "77") (name "Net-(U$8-START)") (class "Default")
      (node (ref "R6") (pin "2") (pinfunction "2_2") (pintype "passive"))
      (node (ref "U$8") (pin "16") (pinfunction "START_16") (pintype "bidirectional"))
    )
    (net (code "78") (name "Net-(U$8-VCAP1)") (class "Default")
      (node (ref "C49") (pin "2") (pinfunction "2_2") (pintype "passive"))
      (node (ref "U$8") (pin "11") (pinfunction "VCAP1_11") (pintype "bidirectional"))
    )
    (net (code "79") (name "Net-(U$8-VCAP2)") (class "Default")
      (node (ref "C48") (pin "2") (pinfunction "2_2") (pintype "passive"))
      (node (ref "U$8") (pin "27") (pinfunction "VCAP2_27") (pintype "bidirectional"))
    )
    (net (code "80") (name "Net-(U$8-VREFP)") (class "Default")
      (node (ref "C50") (pin "2") (pinfunction "2_2") (pintype "passive"))
      (node (ref "C51") (pin "1") (pinfunction "1_1") (pintype "passive"))
      (node (ref "U$8") (pin "9") (pinfunction "VREFP_9") (pintype "bidirectional"))
    )
    (net (code "81") (name "Net-(U$8-~{CS})") (class "Default")
      (node (ref "R7") (pin "2") (pinfunction "2_2") (pintype "passive"))
      (node (ref "U$8") (pin "18") (pinfunction "~{CS}_18") (pintype "bidirectional"))
    )
    (net (code "82") (name "Net-(U$8-~{DRDY})") (class "Default")
      (node (ref "R26") (pin "2") (pinfunction "2_2") (pintype "passive"))
      (node (ref "U$8") (pin "22") (pinfunction "~{DRDY}_22") (pintype "bidirectional"))
    )
    (net (code "83") (name "Net-(U$8-~{PWDN{slash}RESET})") (class "Default")
      (node (ref "R5") (pin "2") (pinfunction "2_2") (pintype "passive"))
      (node (ref "U$8") (pin "15") (pinfunction "~{PWDN/RESET}_15") (pintype "bidirectional"))
    )
    (net (code "84") (name "Net-(U$10-P$1)") (class "Default")
      (node (ref "C24") (pin "1") (pinfunction "1_1") (pintype "passive"))
      (node (ref "C26") (pin "1") (pinfunction "1_1") (pintype "passive"))
      (node (ref "R45") (pin "2") (pinfunction "2_2") (pintype "passive"))
      (node (ref "U$10") (pin "1") (pinfunction "P$1_1") (pintype "bidirectional"))
      (node (ref "U$11") (pin "1") (pinfunction "P$1_1") (pintype "bidirectional"))
      (node (ref "U$6") (pin "5") (pinfunction "OUT_5") (pintype "bidirectional"))
    )
    (net (code "85") (name "Net-(U$13-FB)") (class "Default")
      (node (ref "C39") (pin "2") (pinfunction "2_2") (pintype "passive"))
      (node (ref "U$13") (pin "4") (pinfunction "FB_4") (pintype "bidirectional"))
    )
    (net (code "86") (name "Net-(U$14-NR)") (class "Default")
      (node (ref "C29") (pin "1") (pinfunction "1_1") (pintype "passive"))
      (node (ref "U$14") (pin "4") (pinfunction "NR_4") (pintype "bidirectional"))
    )
    (net (code "87") (name "Net-(U1-SCL)") (class "Default")
      (node (ref "K1") (pin "28") (pinfunction "28_28") (pintype "passive"))
      (node (ref "R1") (pin "1") (pinfunction "1_1") (pintype "passive"))
      (node (ref "U1") (pin "6") (pinfunction "SCL_6") (pintype "input"))
    )
    (net (code "88") (name "Net-(U1-SDA)") (class "Default")
      (node (ref "K1") (pin "27") (pinfunction "27_27") (pintype "passive"))
      (node (ref "R2") (pin "1") (pinfunction "1_1") (pintype "passive"))
      (node (ref "U1") (pin "5") (pinfunction "SDA_5") (pintype "bidirectional"))
    )
    (net (code "89") (name "Net-(U1-WP)") (class "Default")
      (node (ref "R3") (pin "1") (pinfunction "1_1") (pintype "passive"))
      (node (ref "TP3") (pin "TP") (pinfunction "TP_TP") (pintype "input"))
      (node (ref "U1") (pin "7") (pinfunction "WP_7") (pintype "input"))
    )
    (net (code "90") (name "PD_ALM") (class "Default")
      (node (ref "TP9") (pin "P$1") (pinfunction "1_P$1") (pintype "bidirectional"))
      (node (ref "U$3") (pin "23") (pinfunction "PD_ALM_23") (pintype "bidirectional"))
    )
    (net (code "91") (name "RPI_RXD") (class "Default")
      (node (ref "K1") (pin "10") (pinfunction "10_10") (pintype "passive"))
      (node (ref "R36") (pin "2") (pinfunction "2_2") (pintype "passive"))
    )
    (net (code "92") (name "RPI_TXD") (class "Default")
      (node (ref "K1") (pin "8") (pinfunction "8_8") (pintype "passive"))
      (node (ref "R50") (pin "2") (pinfunction "2_2") (pintype "passive"))
    )
    (net (code "93") (name "RX_ANA_SUP") (class "Default")
      (node (ref "C11") (pin "1") (pinfunction "1_1") (pintype "passive"))
      (node (ref "C18") (pin "1") (pinfunction "1_1") (pintype "passive"))
      (node (ref "D2") (pin "3") (pinfunction "A_3") (pintype "passive"))
      (node (ref "D3") (pin "3") (pinfunction "A_3") (pintype "passive"))
      (node (ref "U$3") (pin "33") (pinfunction "RX_ANA_SUP_33") (pintype "bidirectional"))
      (node (ref "U$3") (pin "39") (pinfunction "RX_ANA_SUP_39") (pintype "bidirectional"))
      (node (ref "U$7") (pin "2") (pinfunction "P$2_2") (pintype "bidirectional"))
    )
    (net (code "94") (name "RX_DIG_SUP") (class "Default")
      (node (ref "C12") (pin "1") (pinfunction "1_1") (pintype "passive"))
      (node (ref "C19") (pin "1") (pinfunction "1_1") (pintype "passive"))
      (node (ref "R47") (pin "1") (pinfunction "1_1") (pintype "passive"))
      (node (ref "U$3") (pin "31") (pinfunction "RX_DIG_SUP_31") (pintype "bidirectional"))
      (node (ref "U$9") (pin "2") (pinfunction "P$2_2") (pintype "bidirectional"))
    )
    (net (code "95") (name "SAM_RESETN") (class "Default")
      (node (ref "CON_JTAG1") (pin "10") (pinfunction "10_10") (pintype "bidirectional"))
      (node (ref "IC2") (pin "40") (pinfunction "RESETN_40") (pintype "bidirectional"))
      (node (ref "R9") (pin "2") (pinfunction "2_2") (pintype "passive"))
      (node (ref "U$18") (pin "P$1") (pinfunction "P$1_P$1") (pintype "bidirectional"))
    )
    (net (code "96") (name "SAM_SWDCLK") (class "Default")
      (node (ref "CON_JTAG1") (pin "4") (pinfunction "4_4") (pintype "bidirectional"))
      (node (ref "IC2") (pin "45") (pinfunction "PA30/EIC/SCOM1PAD2/TC1_45") (pintype "bidirectional"))
    )
    (net (code "97") (name "SAM_SWDIO") (class "Default")
      (node (ref "CON_JTAG1") (pin "2") (pinfunction "2_2") (pintype "bidirectional"))
      (node (ref "IC2") (pin "46") (pinfunction "PA31/EIC/SCOM1PAD3/TC1_46") (pintype "bidirectional"))
    )
    (net (code "98") (name "SCL") (class "Default")
      (node (ref "IC2") (pin "32") (pinfunction "PA23/I2C/EIC/SCOM5PAD1+/TC4_32") (pintype "bidirectional"))
      (node (ref "R35") (pin "2") (pinfunction "2_2") (pintype "passive"))
      (node (ref "TP1") (pin "TP") (pinfunction "TP_TP") (pintype "input"))
    )
    (net (code "99") (name "SDA") (class "Default")
      (node (ref "IC2") (pin "31") (pinfunction "PA22/I2C/EIC/SCOM5PAD0+/TC4_31") (pintype "bidirectional"))
      (node (ref "R34") (pin "2") (pinfunction "2_2") (pintype "passive"))
      (node (ref "TP2") (pin "TP") (pinfunction "TP_TP") (pintype "input"))
    )
    (net (code "100") (name "SPO2_CS") (class "Default")
      (node (ref "IC2") (pin "7") (pinfunction "PB8/EIC/AIN2/SCOM4PAD0/TC4_7") (pintype "bidirectional"))
      (node (ref "R28") (pin "1") (pinfunction "1_1") (pintype "passive"))
    )
    (net (code "101") (name "SPO2_DRDY") (class "Default")
      (node (ref "IC2") (pin "3") (pinfunction "PA2/EIC/AIN0_3") (pintype "bidirectional"))
      (node (ref "R27") (pin "1") (pinfunction "1_1") (pintype "passive"))
    )
    (net (code "102") (name "SPO2_MISO") (class "Default")
      (node (ref "IC2") (pin "9") (pinfunction "PA4/EIC/REF/AIN4/SCOM0PAD0/TC0_9") (pintype "bidirectional"))
      (node (ref "R31") (pin "1") (pinfunction "1_1") (pintype "passive"))
    )
    (net (code "103") (name "SPO2_MOSI") (class "Default")
      (node (ref "IC2") (pin "11") (pinfunction "PA6/EIC/AIN6/SCOM0PAD2/TC1_11") (pintype "bidirectional"))
      (node (ref "R29") (pin "1") (pinfunction "1_1") (pintype "passive"))
    )
    (net (code "104") (name "SPO2_SCK") (class "Default")
      (node (ref "IC2") (pin "12") (pinfunction "PA7/EIC/AIN7/SCOM0PAD3/TC1_12") (pintype "bidirectional"))
      (node (ref "R32") (pin "1") (pinfunction "1_1") (pintype "passive"))
    )
    (net (code "105") (name "SPO2_START") (class "Default")
      (node (ref "IC2") (pin "8") (pinfunction "PB9/EIC/AIN3/SCOM4PAD1//TC4_8") (pintype "bidirectional"))
      (node (ref "R33") (pin "2") (pinfunction "2_2") (pintype "passive"))
    )
    (net (code "106") (name "TARGET_USB_N") (class "Default")
      (node (ref "IC2") (pin "33") (pinfunction "PA24/EIC/SCOM3PAD2+/TC5_33") (pintype "bidirectional"))
      (node (ref "R14") (pin "1") (pinfunction "1_1") (pintype "passive"))
    )
    (net (code "107") (name "TARGET_USB_P") (class "Default")
      (node (ref "IC2") (pin "34") (pinfunction "PA25/EIC/SCOM3PAD3+/TC5_34") (pintype "bidirectional"))
      (node (ref "R13") (pin "1") (pinfunction "1_1") (pintype "passive"))
    )
    (net (code "108") (name "TXN") (class "Default")
      (node (ref "D1") (pin "1") (pinfunction "CA_1") (pintype "passive"))
      (node (ref "R40") (pin "2") (pinfunction "2_2") (pintype "passive"))
      (node (ref "X1") (pin "3") (pinfunction "3_3") (pintype "passive"))
    )
    (net (code "109") (name "TXP") (class "Default")
      (node (ref "D5") (pin "1") (pinfunction "CA_1") (pintype "passive"))
      (node (ref "R41") (pin "2") (pinfunction "2_2") (pintype "passive"))
      (node (ref "X1") (pin "2") (pinfunction "2_2") (pintype "passive"))
    )
    (net (code "110") (name "TX_CTRL_SUP") (class "Default")
      (node (ref "C27") (pin "1") (pinfunction "1_1") (pintype "passive"))
      (node (ref "C9") (pin "1") (pinfunction "1_1") (pintype "passive"))
      (node (ref "U$10") (pin "2") (pinfunction "P$2_2") (pintype "bidirectional"))
      (node (ref "U$3") (pin "11") (pinfunction "TX_CTRL_SUP_11") (pintype "bidirectional"))
    )
    (net (code "111") (name "USB_N") (class "Default")
      (node (ref "JP5") (pin "2") (pinfunction "D-_2") (pintype "bidirectional"))
      (node (ref "R14") (pin "2") (pinfunction "2_2") (pintype "passive"))
    )
    (net (code "112") (name "USB_P") (class "Default")
      (node (ref "JP5") (pin "3") (pinfunction "D+_3") (pintype "bidirectional"))
      (node (ref "R13") (pin "2") (pinfunction "2_2") (pintype "passive"))
    )
    (net (code "113") (name "VCC") (class "Default")
      (node (ref "C5") (pin "1") (pinfunction "1_1") (pintype "passive"))
      (node (ref "JMP1") (pin "1") (pinfunction "1_1") (pintype "passive"))
      (node (ref "U$14") (pin "5") (pinfunction "OUT_5") (pintype "bidirectional"))
    )
    (net (code "114") (name "VCCIO") (class "Default")
      (node (ref "C3") (pin "1") (pinfunction "1_1") (pintype "passive"))
      (node (ref "JP5") (pin "1") (pinfunction "VCC_1") (pintype "bidirectional"))
      (node (ref "L1") (pin "1") (pinfunction "1_1") (pintype "passive"))
    )
    (net (code "115") (name "VCM") (class "Default")
      (node (ref "R42") (pin "1") (pinfunction "1_1") (pintype "passive"))
      (node (ref "U$3") (pin "4") (pinfunction "VCM_4") (pintype "bidirectional"))
    )
    (net (code "116") (name "VDDCORE") (class "Default")
      (node (ref "C102") (pin "1") (pinfunction "1_1") (pintype "passive"))
      (node (ref "IC2") (pin "43") (pinfunction "VDDCORE1_43") (pintype "input"))
    )
    (net (code "117") (name "unconnected-(CON_JTAG1-Pad6)") (class "Default")
      (node (ref "CON_JTAG1") (pin "6") (pinfunction "6_6") (pintype "bidirectional"))
    )
    (net (code "118") (name "unconnected-(CON_JTAG1-Pad7)") (class "Default")
      (node (ref "CON_JTAG1") (pin "7") (pinfunction "7_7") (pintype "bidirectional"))
    )
    (net (code "119") (name "unconnected-(CON_JTAG1-Pad8)") (class "Default")
      (node (ref "CON_JTAG1") (pin "8") (pinfunction "8_8") (pintype "bidirectional"))
    )
    (net (code "120") (name "unconnected-(IC2-PA3{slash}EIC{slash}REF{slash}AIN1-Pad4)") (class "Default")
      (node (ref "IC2") (pin "4") (pinfunction "PA3/EIC/REF/AIN1_4") (pintype "bidirectional"))
    )
    (net (code "121") (name "unconnected-(IC2-PA14{slash}XIN{slash}EIC{slash}SCOM2PAD2+{slash}TC3-Pad23)") (class "Default")
      (node (ref "IC2") (pin "23") (pinfunction "PA14/XIN/EIC/SCOM2PAD2+/TC3_23") (pintype "bidirectional"))
    )
    (net (code "122") (name "unconnected-(IC2-PA21{slash}EIC{slash}SCOM5PAD3+-Pad30)") (class "Default")
      (node (ref "IC2") (pin "30") (pinfunction "PA21/EIC/SCOM5PAD3+_30") (pintype "bidirectional"))
    )
    (net (code "123") (name "unconnected-(IC2-PA27{slash}EIC-Pad39)") (class "Default")
      (node (ref "IC2") (pin "39") (pinfunction "PA27/EIC_39") (pintype "bidirectional"))
    )
    (net (code "124") (name "unconnected-(IC2-PA28{slash}EIC-Pad41)") (class "Default")
      (node (ref "IC2") (pin "41") (pinfunction "PA28/EIC_41") (pintype "bidirectional"))
    )
    (net (code "125") (name "unconnected-(IC2-PB2{slash}EIC{slash}AIN10{slash}SCOM5PAD0-Pad47)") (class "Default")
      (node (ref "IC2") (pin "47") (pinfunction "PB2/EIC/AIN10/SCOM5PAD0_47") (pintype "bidirectional"))
    )
    (net (code "126") (name "unconnected-(IC2-PB3{slash}EIC{slash}AIN11{slash}SCOM5PAD1-Pad48)") (class "Default")
      (node (ref "IC2") (pin "48") (pinfunction "PB3/EIC/AIN11/SCOM5PAD1_48") (pintype "bidirectional"))
    )
    (net (code "127") (name "unconnected-(IC2-PB10{slash}EIC{slash}SCOM4PAD2{slash}TC5-Pad19)") (class "Default")
      (node (ref "IC2") (pin "19") (pinfunction "PB10/EIC/SCOM4PAD2/TC5_19") (pintype "bidirectional"))
    )
    (net (code "128") (name "unconnected-(IC2-PB11{slash}EIC{slash}SCOM4PAD3{slash}TC5-Pad20)") (class "Default")
      (node (ref "IC2") (pin "20") (pinfunction "PB11/EIC/SCOM4PAD3/TC5_20") (pintype "bidirectional"))
    )
    (net (code "129") (name "unconnected-(K1-Pad1)") (class "Default")
      (node (ref "K1") (pin "1") (pinfunction "1_1") (pintype "passive"))
    )
    (net (code "130") (name "unconnected-(K1-Pad3)") (class "Default")
      (node (ref "K1") (pin "3") (pinfunction "3_3") (pintype "passive"))
    )
    (net (code "131") (name "unconnected-(K1-Pad5)") (class "Default")
      (node (ref "K1") (pin "5") (pinfunction "5_5") (pintype "passive"))
    )
    (net (code "132") (name "unconnected-(K1-Pad7)") (class "Default")
      (node (ref "K1") (pin "7") (pinfunction "7_7") (pintype "passive"))
    )
    (net (code "133") (name "unconnected-(K1-Pad11)") (class "Default")
      (node (ref "K1") (pin "11") (pinfunction "11_11") (pintype "passive"))
    )
    (net (code "134") (name "unconnected-(K1-Pad12)") (class "Default")
      (node (ref "K1") (pin "12") (pinfunction "12_12") (pintype "passive"))
    )
    (net (code "135") (name "unconnected-(K1-Pad13)") (class "Default")
      (node (ref "K1") (pin "13") (pinfunction "13_13") (pintype "passive"))
    )
    (net (code "136") (name "unconnected-(K1-Pad15)") (class "Default")
      (node (ref "K1") (pin "15") (pinfunction "15_15") (pintype "passive"))
    )
    (net (code "137") (name "unconnected-(K1-Pad16)") (class "Default")
      (node (ref "K1") (pin "16") (pinfunction "16_16") (pintype "passive"))
    )
    (net (code "138") (name "unconnected-(K1-Pad17)") (class "Default")
      (node (ref "K1") (pin "17") (pinfunction "17_17") (pintype "passive"))
    )
    (net (code "139") (name "unconnected-(K1-Pad18)") (class "Default")
      (node (ref "K1") (pin "18") (pinfunction "18_18") (pintype "passive"))
    )
    (net (code "140") (name "unconnected-(K1-Pad19)") (class "Default")
      (node (ref "K1") (pin "19") (pinfunction "19_19") (pintype "passive"))
    )
    (net (code "141") (name "unconnected-(K1-Pad21)") (class "Default")
      (node (ref "K1") (pin "21") (pinfunction "21_21") (pintype "passive"))
    )
    (net (code "142") (name "unconnected-(K1-Pad22)") (class "Default")
      (node (ref "K1") (pin "22") (pinfunction "22_22") (pintype "passive"))
    )
    (net (code "143") (name "unconnected-(K1-Pad23)") (class "Default")
      (node (ref "K1") (pin "23") (pinfunction "23_23") (pintype "passive"))
    )
    (net (code "144") (name "unconnected-(K1-Pad24)") (class "Default")
      (node (ref "K1") (pin "24") (pinfunction "24_24") (pintype "passive"))
    )
    (net (code "145") (name "unconnected-(K1-Pad26)") (class "Default")
      (node (ref "K1") (pin "26") (pinfunction "26_26") (pintype "passive"))
    )
    (net (code "146") (name "unconnected-(K1-Pad29)") (class "Default")
      (node (ref "K1") (pin "29") (pinfunction "29_29") (pintype "passive"))
    )
    (net (code "147") (name "unconnected-(K1-Pad31)") (class "Default")
      (node (ref "K1") (pin "31") (pinfunction "31_31") (pintype "passive"))
    )
    (net (code "148") (name "unconnected-(K1-Pad32)") (class "Default")
      (node (ref "K1") (pin "32") (pinfunction "32_32") (pintype "passive"))
    )
    (net (code "149") (name "unconnected-(K1-Pad33)") (class "Default")
      (node (ref "K1") (pin "33") (pinfunction "33_33") (pintype "passive"))
    )
    (net (code "150") (name "unconnected-(K1-Pad35)") (class "Default")
      (node (ref "K1") (pin "35") (pinfunction "35_35") (pintype "passive"))
    )
    (net (code "151") (name "unconnected-(K1-Pad36)") (class "Default")
      (node (ref "K1") (pin "36") (pinfunction "36_36") (pintype "passive"))
    )
    (net (code "152") (name "unconnected-(K1-Pad37)") (class "Default")
      (node (ref "K1") (pin "37") (pinfunction "37_37") (pintype "passive"))
    )
    (net (code "153") (name "unconnected-(K1-Pad38)") (class "Default")
      (node (ref "K1") (pin "38") (pinfunction "38_38") (pintype "passive"))
    )
    (net (code "154") (name "unconnected-(K1-Pad40)") (class "Default")
      (node (ref "K1") (pin "40") (pinfunction "40_40") (pintype "passive"))
    )
    (net (code "155") (name "unconnected-(U$3-DNC-Pad5)") (class "Default")
      (node (ref "U$3") (pin "5") (pinfunction "DNC_5") (pintype "bidirectional"))
    )
    (net (code "156") (name "unconnected-(U$3-DNC-Pad6)") (class "Default")
      (node (ref "U$3") (pin "6") (pinfunction "DNC_6") (pintype "bidirectional"))
    )
    (net (code "157") (name "unconnected-(U$3-DNC-Pad10)") (class "Default")
      (node (ref "U$3") (pin "10") (pinfunction "DNC_10") (pintype "bidirectional"))
    )
    (net (code "158") (name "unconnected-(U$3-DNC-Pad34)") (class "Default")
      (node (ref "U$3") (pin "34") (pinfunction "DNC_34") (pintype "bidirectional"))
    )
    (net (code "159") (name "unconnected-(U$3-DNC-Pad35)") (class "Default")
      (node (ref "U$3") (pin "35") (pinfunction "DNC_35") (pintype "bidirectional"))
    )
    (net (code "160") (name "unconnected-(U$3-RSVD-Pad9)") (class "Default")
      (node (ref "U$3") (pin "9") (pinfunction "RSVD_9") (pintype "bidirectional"))
    )
    (net (code "161") (name "unconnected-(U$6-N{slash}C-Pad2)") (class "Default")
      (node (ref "U$6") (pin "2") (pinfunction "N/C_2") (pintype "bidirectional"))
    )
    (net (code "162") (name "unconnected-(U$6-N{slash}C-Pad7)") (class "Default")
      (node (ref "U$6") (pin "7") (pinfunction "N/C_7") (pintype "bidirectional"))
    )
    (net (code "163") (name "unconnected-(U$8-GPIO1-Pad26)") (class "Default")
      (node (ref "U$8") (pin "26") (pinfunction "GPIO1_26") (pintype "bidirectional"))
    )
    (net (code "164") (name "unconnected-(U$8-GPIO2-Pad25)") (class "Default")
      (node (ref "U$8") (pin "25") (pinfunction "GPIO2_25") (pintype "bidirectional"))
    )
    (net (code "165") (name "unconnected-(U$8-TERM-PadP$33)") (class "Default")
      (node (ref "U$8") (pin "P$33") (pinfunction "TERM_P$33") (pintype "bidirectional"))
    )
    (net (code "166") (name "unconnected-(X1-Pad1)") (class "Default")
      (node (ref "X1") (pin "1") (pinfunction "1_1") (pintype "passive"))
    )
    (net (code "167") (name "unconnected-(X1-Pad4)") (class "Default")
      (node (ref "X1") (pin "4") (pinfunction "4_4") (pintype "passive"))
    )
    (net (code "168") (name "unconnected-(X1-Pad6)") (class "Default")
      (node (ref "X1") (pin "6") (pinfunction "6_6") (pintype "passive"))
    )
    (net (code "169") (name "unconnected-(X1-Pad8)") (class "Default")
      (node (ref "X1") (pin "8") (pinfunction "8_8") (pintype "passive"))
    )
    (net (code "170") (name "~{ADC_RESET}") (class "Default")
      (node (ref "R47") (pin "2") (pinfunction "2_2") (pintype "passive"))
      (node (ref "U$3") (pin "29") (pinfunction "~{RESET}_29") (pintype "bidirectional"))
    )
  )
)
